# tailLite.net
KiCad netlist of a schematic drawn in Altium Designer
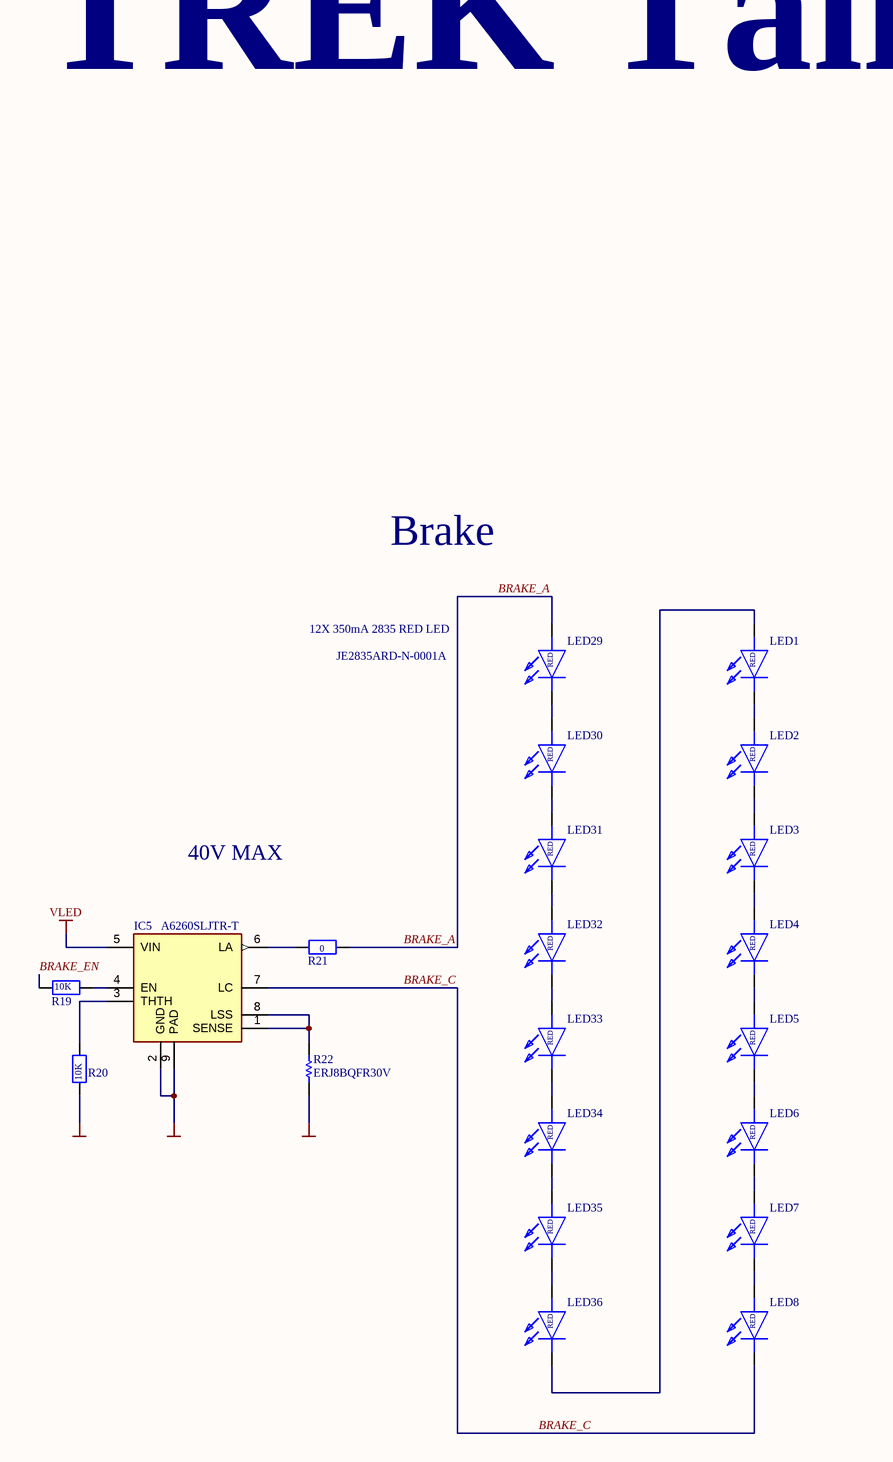
[diagram p0: tailLite.SchDoc, top left]
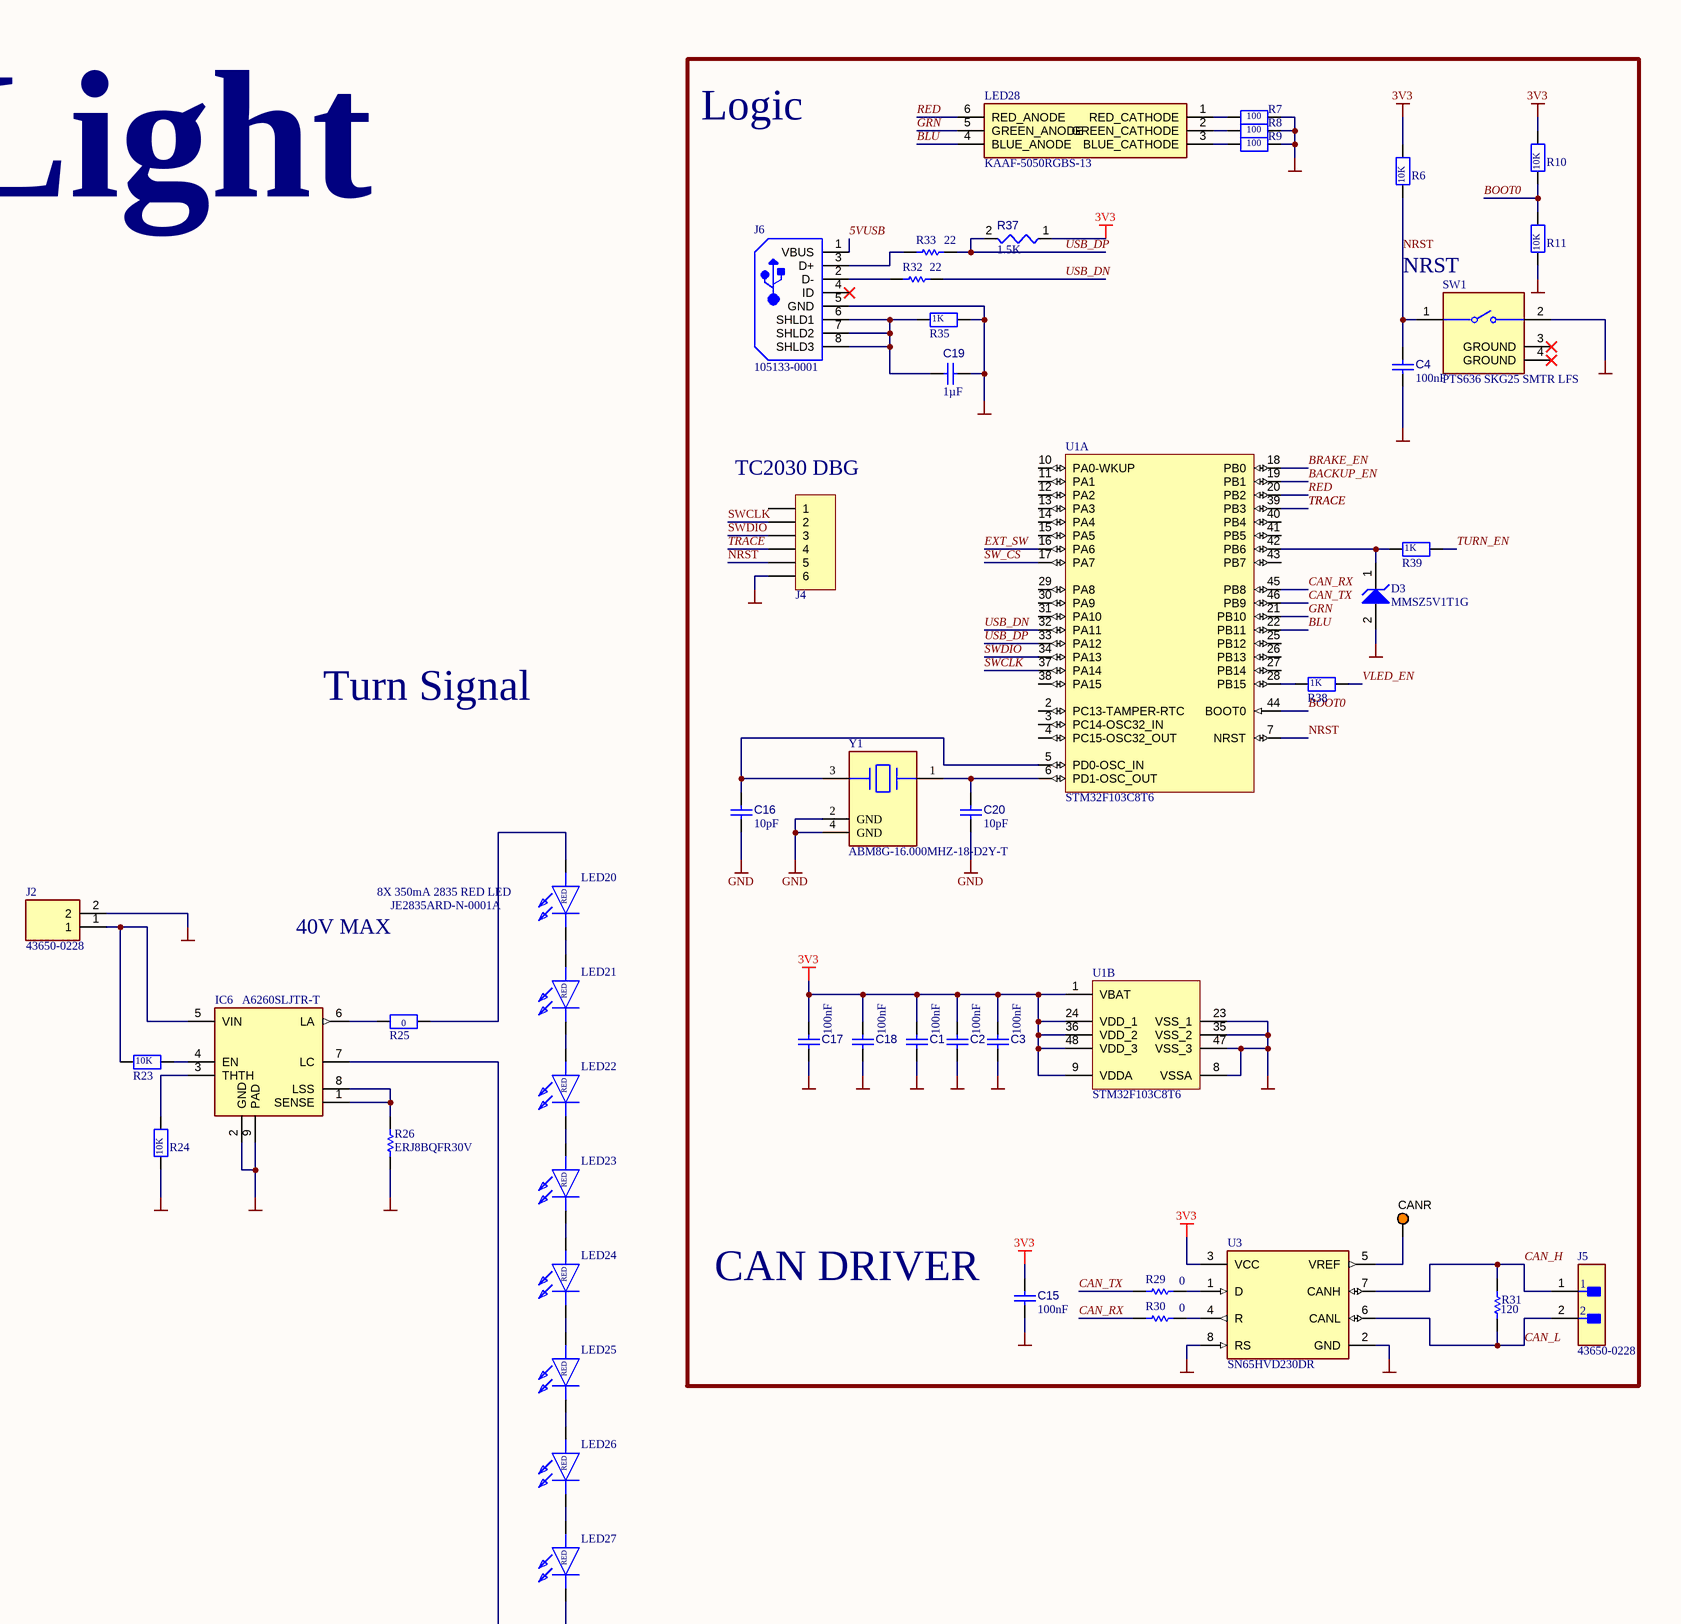
[diagram p1: tailLite.SchDoc, top right]
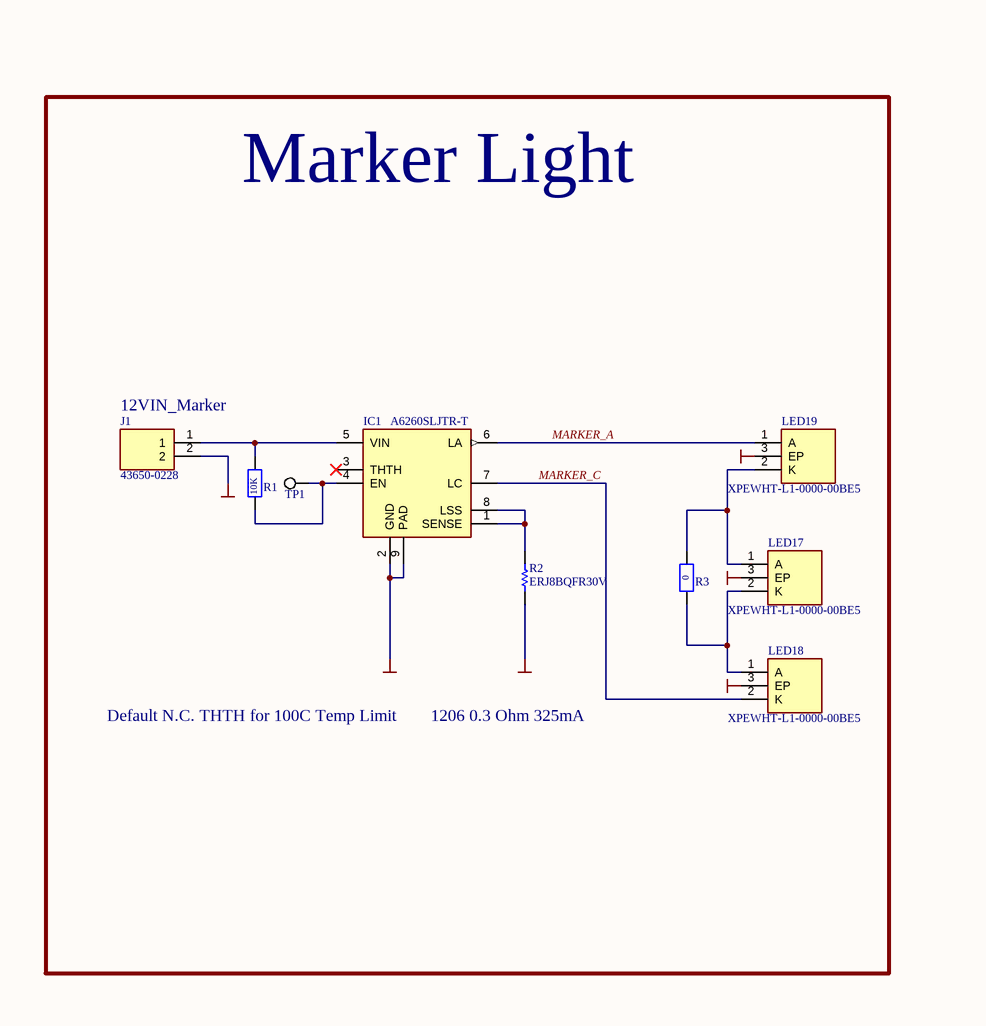
[diagram p2: tailLite.SchDoc, bottom left]
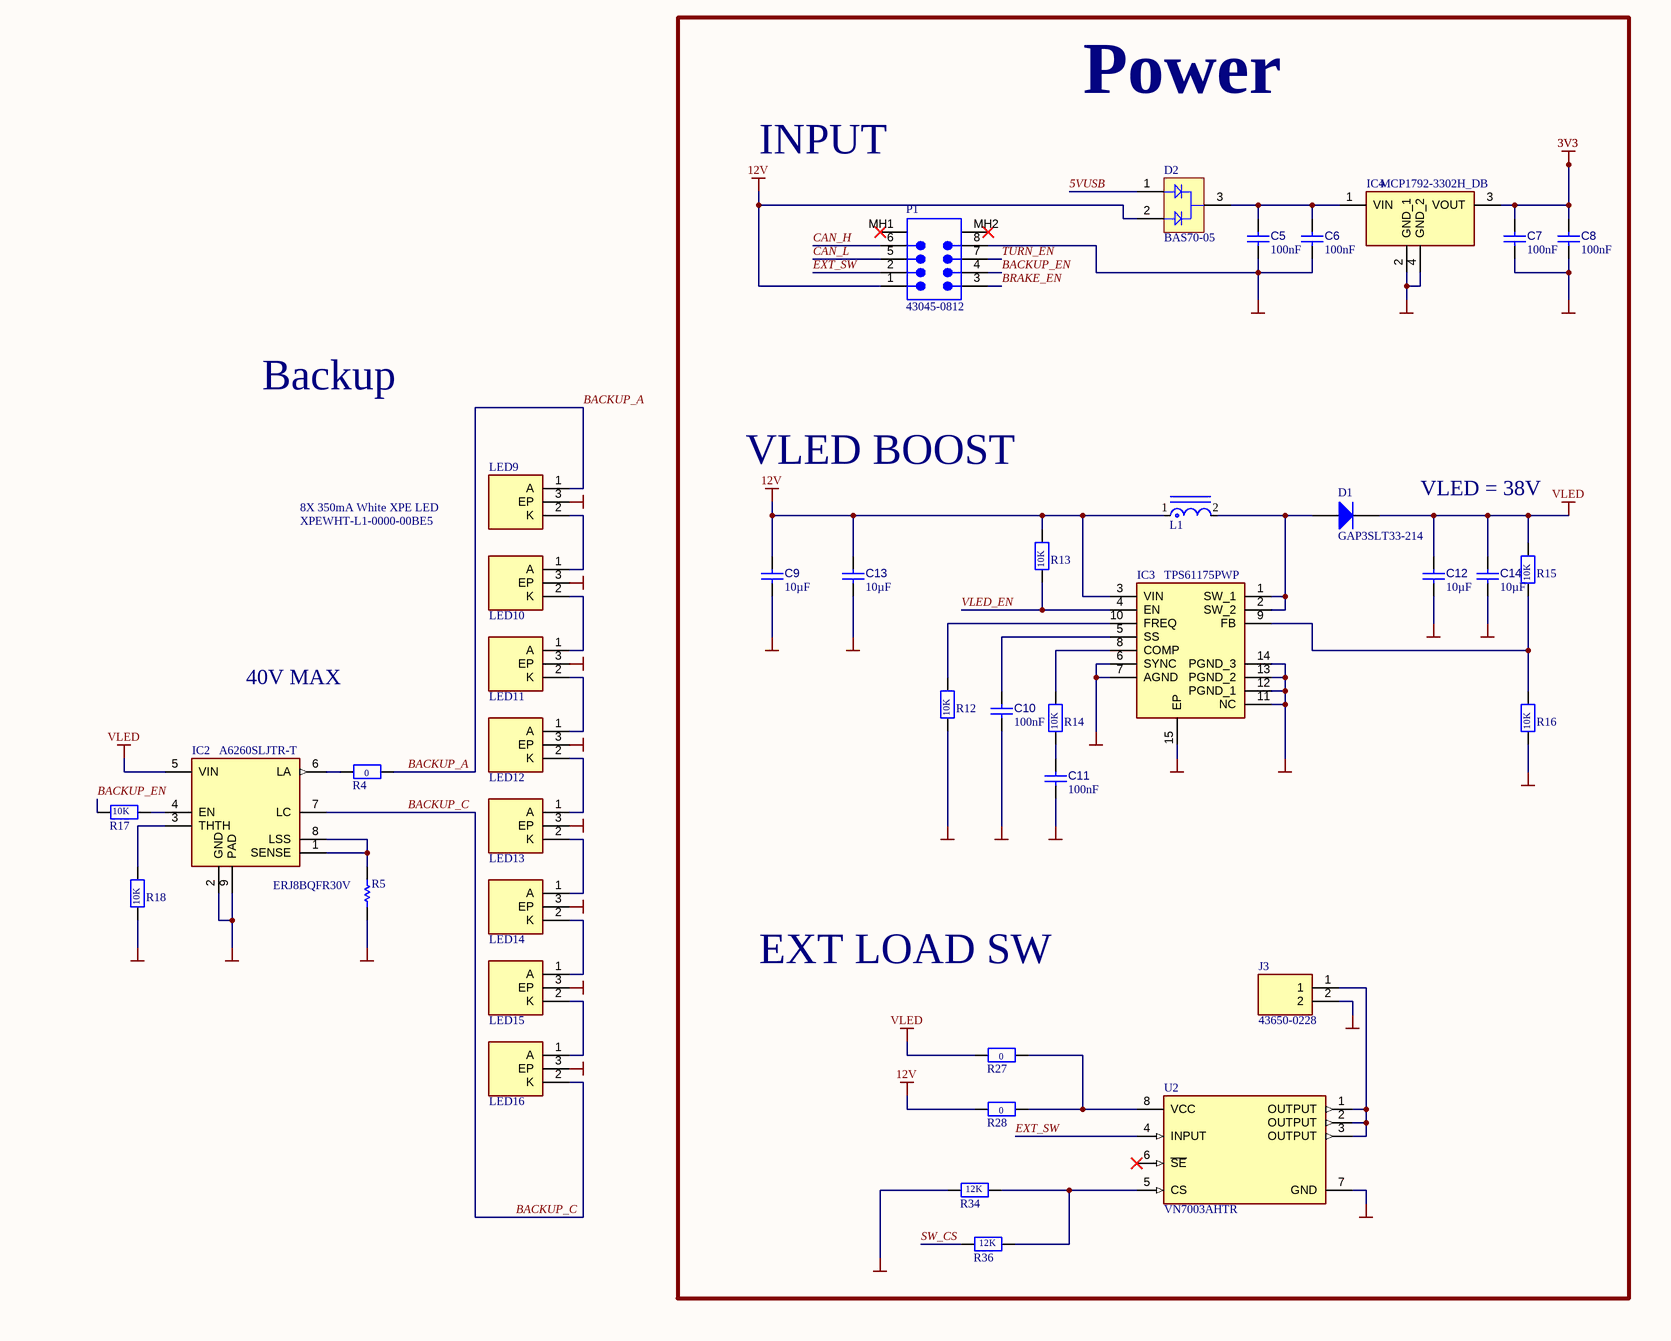
[diagram p3: tailLite.SchDoc, bottom right]

(export (version "E")
  (design (tool "Eeschema 10.0.6"))
  (components
    (comp (ref "C1")
      (value "100nF")
      (footprint "CAPC1608X90X40NL10T20")
      (description "Chip Capacitor, 100 nF, +/- 10%, 50 V, 0603 (1608 Metric)")
      (fields (field (name "TOLERANCE") "10%") (field (name "Comment") "Capacitor 100 nF +/-10% 50 V 0603"))
      (libsource (lib "Nebraska Instruments") (part "CAP-NP-2"))
    )
    (comp (ref "C2")
      (value "100nF")
      (footprint "CAPC1608X90X40NL10T20")
      (description "Chip Capacitor, 100 nF, +/- 10%, 50 V, 0603 (1608 Metric)")
      (fields (field (name "TOLERANCE") "10%") (field (name "Comment") "Capacitor 100 nF +/-10% 50 V 0603"))
      (libsource (lib "Nebraska Instruments") (part "CAP-NP-2"))
    )
    (comp (ref "C3")
      (value "100nF")
      (footprint "CAPC1608X90X40NL10T20")
      (description "Chip Capacitor, 100 nF, +/- 10%, 50 V, 0603 (1608 Metric)")
      (fields (field (name "TOLERANCE") "10%") (field (name "Comment") "Capacitor 100 nF +/-10% 50 V 0603"))
      (libsource (lib "Nebraska Instruments") (part "CAP-NP-2"))
    )
    (comp (ref "C4")
      (value "100nF")
      (footprint "CAPC1608X90X40NL10T20")
      (description "Chip Capacitor, 100 nF, +/- 10%, 50 V, 0603 (1608 Metric)")
      (fields (field (name "TOLERANCE") "10%") (field (name "Comment") "Capacitor 100 nF +/-10% 50 V 0603"))
      (libsource (lib "Nebraska Instruments") (part "CAP-NP-2"))
    )
    (comp (ref "C5")
      (value "100nF")
      (footprint "CAPC1608X90X40NL10T20")
      (description "Chip Capacitor, 100 nF, +/- 10%, 50 V, 0603 (1608 Metric)")
      (fields (field (name "TOLERANCE") "10%") (field (name "Comment") "Capacitor 100 nF +/-10% 50 V 0603"))
      (libsource (lib "Nebraska Instruments") (part "CAP-NP-2"))
    )
    (comp (ref "C6")
      (value "100nF")
      (footprint "CAPC1608X90X40NL10T20")
      (description "Chip Capacitor, 100 nF, +/- 10%, 50 V, 0603 (1608 Metric)")
      (fields (field (name "TOLERANCE") "10%") (field (name "Comment") "Capacitor 100 nF +/-10% 50 V 0603"))
      (libsource (lib "Nebraska Instruments") (part "CAP-NP-2"))
    )
    (comp (ref "C7")
      (value "100nF")
      (footprint "CAPC1608X90X40NL10T20")
      (description "Chip Capacitor, 100 nF, +/- 10%, 50 V, 0603 (1608 Metric)")
      (fields (field (name "TOLERANCE") "10%") (field (name "Comment") "Capacitor 100 nF +/-10% 50 V 0603"))
      (libsource (lib "Nebraska Instruments") (part "CAP-NP-2"))
    )
    (comp (ref "C8")
      (value "100nF")
      (footprint "CAPC1608X90X40NL10T20")
      (description "Chip Capacitor, 100 nF, +/- 10%, 50 V, 0603 (1608 Metric)")
      (fields (field (name "TOLERANCE") "10%") (field (name "Comment") "Capacitor 100 nF +/-10% 50 V 0603"))
      (libsource (lib "Nebraska Instruments") (part "CAP-NP-2"))
    )
    (comp (ref "C9")
      (value "10µF")
      (footprint "CAPC3216X180X50NL20T25")
      (description "Chip Capacitor, 10 uF, +/- 10%, 16 V, 1206 (3216 Metric)")
      (fields (field (name "TOLERANCE") "10%") (field (name "Comment") "Capacitor 10 uF +/- 10% 16 V 1206"))
      (libsource (lib "Nebraska Instruments") (part "CAP-NP-2"))
    )
    (comp (ref "C10")
      (value "100nF")
      (footprint "CAPC1608X90X40NL10T20")
      (description "Chip Capacitor, 100 nF, +/- 10%, 50 V, 0603 (1608 Metric)")
      (fields (field (name "TOLERANCE") "10%") (field (name "Comment") "Capacitor 100 nF +/-10% 50 V 0603"))
      (libsource (lib "Nebraska Instruments") (part "CAP-NP-2"))
    )
    (comp (ref "C11")
      (value "100nF")
      (footprint "CAPC1608X90X40NL10T20")
      (description "Chip Capacitor, 100 nF, +/- 10%, 50 V, 0603 (1608 Metric)")
      (fields (field (name "TOLERANCE") "10%") (field (name "Comment") "Capacitor 100 nF +/-10% 50 V 0603"))
      (libsource (lib "Nebraska Instruments") (part "CAP-NP-2"))
    )
    (comp (ref "C12")
      (value "10µF")
      (footprint "CAPC3216X180X50NL20T25")
      (description "Chip Capacitor, 10 uF, +/- 10%, 16 V, 1206 (3216 Metric)")
      (fields (field (name "TOLERANCE") "10%") (field (name "Comment") "Capacitor 10 uF +/- 10% 16 V 1206"))
      (libsource (lib "Nebraska Instruments") (part "CAP-NP-2"))
    )
    (comp (ref "C13")
      (value "10µF")
      (footprint "CAPC3216X180X50NL20T25")
      (description "Chip Capacitor, 10 uF, +/- 10%, 16 V, 1206 (3216 Metric)")
      (fields (field (name "TOLERANCE") "10%") (field (name "Comment") "Capacitor 10 uF +/- 10% 16 V 1206"))
      (libsource (lib "Nebraska Instruments") (part "CAP-NP-2"))
    )
    (comp (ref "C14")
      (value "10µF")
      (footprint "CAPC3216X180X50NL20T25")
      (description "Chip Capacitor, 10 uF, +/- 10%, 16 V, 1206 (3216 Metric)")
      (fields (field (name "TOLERANCE") "10%") (field (name "Comment") "Capacitor 10 uF +/- 10% 16 V 1206"))
      (libsource (lib "Nebraska Instruments") (part "CAP-NP-2"))
    )
    (comp (ref "C15")
      (value "100nF")
      (footprint "CAPC1608X90X40NL10T20")
      (description "Chip Capacitor, 100 nF, +/- 10%, 50 V, 0603 (1608 Metric)")
      (fields (field (name "TOLERANCE") "10%") (field (name "Comment") "Capacitor 100 nF +/-10% 50 V 0603"))
      (libsource (lib "Nebraska Instruments") (part "CAP-NP-2"))
    )
    (comp (ref "C16")
      (value "10pF")
      (footprint "CAPC1608X87X35NL15T15")
      (description "Chip Capacitor, 10 pF, +/- 0.25 pF, 50 V, 0603 (1608 Metric)")
      (fields
        (field (name "TOLERANCE") "0.25%")
        (field (name "Comment") "Capacitor 10 pF +/- 0.25 pF 50 V 0603")
      )
      (libsource (lib "Nebraska Instruments") (part "CAP-NP-2"))
    )
    (comp (ref "C17")
      (value "100nF")
      (footprint "CAPC1608X90X40NL10T20")
      (description "Chip Capacitor, 100 nF, +/- 10%, 50 V, 0603 (1608 Metric)")
      (fields (field (name "TOLERANCE") "10%") (field (name "Comment") "Capacitor 100 nF +/-10% 50 V 0603"))
      (libsource (lib "Nebraska Instruments") (part "CAP-NP-2"))
    )
    (comp (ref "C18")
      (value "100nF")
      (footprint "CAPC1608X90X40NL10T20")
      (description "Chip Capacitor, 100 nF, +/- 10%, 50 V, 0603 (1608 Metric)")
      (fields (field (name "TOLERANCE") "10%") (field (name "Comment") "Capacitor 100 nF +/-10% 50 V 0603"))
      (libsource (lib "Nebraska Instruments") (part "CAP-NP-2"))
    )
    (comp (ref "C19")
      (value "1µF")
      (footprint "CAPC1608X90X35ML15T15")
      (description "Chip Capacitor, 1 uF, +/- 10%, 16 V, 0603 (1608 Metric)")
      (fields (field (name "TOLERANCE") "10%") (field (name "Comment") "Capacitor 1uF +/- 10% 16V 0603"))
      (libsource (lib "Nebraska Instruments") (part "CAP-NP-2"))
    )
    (comp (ref "C20")
      (value "10pF")
      (footprint "CAPC1608X87X35NL15T15")
      (description "Chip Capacitor, 10 pF, +/- 0.25 pF, 50 V, 0603 (1608 Metric)")
      (fields
        (field (name "TOLERANCE") "0.25%")
        (field (name "Comment") "Capacitor 10 pF +/- 0.25 pF 50 V 0603")
      )
      (libsource (lib "Nebraska Instruments") (part "CAP-NP-2"))
    )
    (comp (ref "CANR")
      (value "5003")
      (footprint "KSTN-5003")
      (description "Test Point, Orange, Height 4.6 mm, Tail Length 3 mm, 1-Pin THD, RoHS")
      (fields (field (name "MANUFACTURER") "Keystone"))
      (libsource (lib "Nebraska Instruments") (part "TESTPOINT_ORANGE"))
    )
    (comp (ref "D1")
      (value "GAP3SLT33-214")
      (footprint "GESC-GAP3SLT33-214-2_V")
      (fields (field (name "MANUFACTURER") "GeneSiCSemiconductor"))
      (libsource (lib "Altium Content Vault") (part "D-AK-2"))
    )
    (comp (ref "D2")
      (value "BAS70-05")
      (footprint "INF-SOT23_N")
      (description "Rectifier Diode Schottky Si 0.07A Automotive 3-Pin SOT-23 T/R")
      (libsource (lib "Nebraska Instruments") (part "INF-D_A1A2K3-3_A"))
    )
    (comp (ref "D3")
      (value "MMSZ5V1T1G")
      (footprint "ONSC-SOD-123-2-425-04_V")
      (description "Zener Diode Single 5.1V 5% 60Ohm 500mW 2-Pin SOD-123 T/R")
      (libsource (lib "Nebraska Instruments") (part "MMSZ5V1T1G"))
    )
    (comp (ref "IC1")
      (value "A6260SLJTR-T")
      (footprint "SamacSys:SOIC127P600X170-9N")
      (description "Integrated Circuit")
      (libsource (lib "") (part "A6260SLJTR-T_1"))
    )
    (comp (ref "IC2")
      (value "A6260SLJTR-T")
      (footprint "SamacSys:SOIC127P600X170-9N")
      (description "Integrated Circuit")
      (libsource (lib "*") (part "A6260SLJTR-T"))
    )
    (comp (ref "IC3")
      (value "TPS61175PWP")
      (footprint "SamacSys:SOP65P640X120-15N")
      (description "Integrated Circuit")
      (fields (field (name "MOUSER PART NUMBER") "595-TPS61175PWP"))
      (libsource (lib "*") (part "TPS61175PWP"))
    )
    (comp (ref "IC4")
      (value "MCP1792-3302H_DB")
      (footprint "SOT230P700X180-4N")
      (description "LDO Voltage Regulators High input voltage regulator 3.3V 3Ld SOT-223")
      (fields
        (field (name "MANUFACTURER_PART_NUMBER") "MCP1792-3302H/DB")
        (field (name "MOUSER PART NUMBER") "579-MCP1792-3302HDB")
      )
      (libsource (lib "Nebraska Instruments") (part "MCP1792-5002H_DB"))
    )
    (comp (ref "IC5")
      (value "A6260SLJTR-T")
      (footprint "SamacSys:SOIC127P600X170-9N")
      (description "Integrated Circuit")
      (libsource (lib "*") (part "A6260SLJTR-T"))
    )
    (comp (ref "IC6")
      (value "A6260SLJTR-T")
      (footprint "SamacSys:SOIC127P600X170-9N")
      (description "Integrated Circuit")
      (libsource (lib "*") (part "A6260SLJTR-T"))
    )
    (comp (ref "J1")
      (value "43650-0228")
      (footprint "SamacSys:43650-02YY_272829")
      (description "Connector")
      (fields (field (name "MOUSER PART NUMBER") "538-43650-0228"))
      (libsource (lib "*") (part "43650-0228"))
    )
    (comp (ref "J2")
      (value "43650-0228")
      (footprint "SamacSys:43650-02YY_272829")
      (description "Connector")
      (fields (field (name "MOUSER PART NUMBER") "538-43650-0228"))
      (libsource (lib "") (part "43650-0228_1"))
    )
    (comp (ref "J3")
      (value "43650-0228")
      (footprint "SamacSys:43650-02YY_272829")
      (description "Connector")
      (fields (field (name "MOUSER PART NUMBER") "538-43650-0228"))
      (libsource (lib "*") (part "43650-0228"))
    )
    (comp (ref "J4")
      (value "ICSP")
      (footprint "TC2030-MCP-NL")
      (libsource (lib "Nebraska Instruments") (part "ICSP"))
    )
    (comp (ref "J5")
      (value "43650-0228")
      (footprint "FP-43650-0228-MFG")
      (description "CONN HEADER VERT 2POS 3MM")
      (libsource (lib "Altium Content Vault") (part "3bc925449376181038e59eaffc5286c"))
    )
    (comp (ref "J6")
      (value "105133-0001")
      (footprint "MOLX-105133-0001_V")
      (description "Conn Micro USB 2.0 Type B RCP 5 POS 0.65mm Solder ST SMD 5 Terminal 1 Port Micro-USB T/R")
      (libsource (lib "Nebraska Instruments") (part "USB-5-3SHLD"))
    )
    (comp (ref "L1")
      (value "HCM0703-3R3-R")
      (footprint "FP-HCM0703-MFG")
      (description "Inductor Power Shielded Wirewound 3.3uH/1.98uH 20% 100KHz Powdered Iron 6A 30mOhm DCR T/R")
      (libsource (lib "Nebraska Instruments") (part "39f40dd458ca4f5319b423cc0fb7879"))
    )
    (comp (ref "LED1")
      (value "JE2835ARD-N-0001A")
      (footprint "JE2835ARDN0001A0000N0000001")
      (description "LED Lighting Color J Red-Orange 615nm (610nm ~ 620nm) 1411 (3528 Metric)")
      (fields
        (field (name "MANUFACTURER_PART_NUMBER") "JE2835ARD-N-0001A0000-N0000001")
        (field (name "MOUSER PART NUMBER") "941-JE2835ARDN01AN")
      )
      (libsource (lib "Nebraska Instruments") (part "JE2835ARY-N-0002A0000-N0000001"))
    )
    (comp (ref "LED2")
      (value "JE2835ARD-N-0001A")
      (footprint "JE2835ARDN0001A0000N0000001")
      (description "LED Lighting Color J Red-Orange 615nm (610nm ~ 620nm) 1411 (3528 Metric)")
      (fields
        (field (name "MANUFACTURER_PART_NUMBER") "JE2835ARD-N-0001A0000-N0000001")
        (field (name "MOUSER PART NUMBER") "941-JE2835ARDN01AN")
      )
      (libsource (lib "Nebraska Instruments") (part "JE2835ARY-N-0002A0000-N0000001"))
    )
    (comp (ref "LED3")
      (value "JE2835ARD-N-0001A")
      (footprint "JE2835ARDN0001A0000N0000001")
      (description "LED Lighting Color J Red-Orange 615nm (610nm ~ 620nm) 1411 (3528 Metric)")
      (fields
        (field (name "MANUFACTURER_PART_NUMBER") "JE2835ARD-N-0001A0000-N0000001")
        (field (name "MOUSER PART NUMBER") "941-JE2835ARDN01AN")
      )
      (libsource (lib "Nebraska Instruments") (part "JE2835ARY-N-0002A0000-N0000001"))
    )
    (comp (ref "LED4")
      (value "JE2835ARD-N-0001A")
      (footprint "JE2835ARDN0001A0000N0000001")
      (description "LED Lighting Color J Red-Orange 615nm (610nm ~ 620nm) 1411 (3528 Metric)")
      (fields
        (field (name "MANUFACTURER_PART_NUMBER") "JE2835ARD-N-0001A0000-N0000001")
        (field (name "MOUSER PART NUMBER") "941-JE2835ARDN01AN")
      )
      (libsource (lib "Nebraska Instruments") (part "JE2835ARY-N-0002A0000-N0000001"))
    )
    (comp (ref "LED5")
      (value "JE2835ARD-N-0001A")
      (footprint "JE2835ARDN0001A0000N0000001")
      (description "LED Lighting Color J Red-Orange 615nm (610nm ~ 620nm) 1411 (3528 Metric)")
      (fields
        (field (name "MANUFACTURER_PART_NUMBER") "JE2835ARD-N-0001A0000-N0000001")
        (field (name "MOUSER PART NUMBER") "941-JE2835ARDN01AN")
      )
      (libsource (lib "Nebraska Instruments") (part "JE2835ARY-N-0002A0000-N0000001"))
    )
    (comp (ref "LED6")
      (value "JE2835ARD-N-0001A")
      (footprint "JE2835ARDN0001A0000N0000001")
      (description "LED Lighting Color J Red-Orange 615nm (610nm ~ 620nm) 1411 (3528 Metric)")
      (fields
        (field (name "MANUFACTURER_PART_NUMBER") "JE2835ARD-N-0001A0000-N0000001")
        (field (name "MOUSER PART NUMBER") "941-JE2835ARDN01AN")
      )
      (libsource (lib "Nebraska Instruments") (part "JE2835ARY-N-0002A0000-N0000001"))
    )
    (comp (ref "LED7")
      (value "JE2835ARD-N-0001A")
      (footprint "JE2835ARDN0001A0000N0000001")
      (description "LED Lighting Color J Red-Orange 615nm (610nm ~ 620nm) 1411 (3528 Metric)")
      (fields
        (field (name "MANUFACTURER_PART_NUMBER") "JE2835ARD-N-0001A0000-N0000001")
        (field (name "MOUSER PART NUMBER") "941-JE2835ARDN01AN")
      )
      (libsource (lib "Nebraska Instruments") (part "JE2835ARY-N-0002A0000-N0000001"))
    )
    (comp (ref "LED8")
      (value "JE2835ARD-N-0001A")
      (footprint "JE2835ARDN0001A0000N0000001")
      (description "LED Lighting Color J Red-Orange 615nm (610nm ~ 620nm) 1411 (3528 Metric)")
      (fields
        (field (name "MANUFACTURER_PART_NUMBER") "JE2835ARD-N-0001A0000-N0000001")
        (field (name "MOUSER PART NUMBER") "941-JE2835ARDN01AN")
      )
      (libsource (lib "Nebraska Instruments") (part "JE2835ARY-N-0002A0000-N0000001"))
    )
    (comp (ref "LED9")
      (value "XPEWHT-L1-0000-00BE5")
      (footprint "XPEWHTL1000000BE5")
      (description "LED")
      (fields (field (name "MOUSER PART NUMBER") "941-XPEWHTL100BE5"))
      (libsource (lib "Nebraska Instruments") (part "XPEWHT-L1-0000-00BE5"))
    )
    (comp (ref "LED10")
      (value "XPEWHT-L1-0000-00BE5")
      (footprint "XPEWHTL1000000BE5")
      (description "LED")
      (fields (field (name "MOUSER PART NUMBER") "941-XPEWHTL100BE5"))
      (libsource (lib "Nebraska Instruments") (part "XPEWHT-L1-0000-00BE5"))
    )
    (comp (ref "LED11")
      (value "XPEWHT-L1-0000-00BE5")
      (footprint "XPEWHTL1000000BE5")
      (description "LED")
      (fields (field (name "MOUSER PART NUMBER") "941-XPEWHTL100BE5"))
      (libsource (lib "Nebraska Instruments") (part "XPEWHT-L1-0000-00BE5"))
    )
    (comp (ref "LED12")
      (value "XPEWHT-L1-0000-00BE5")
      (footprint "XPEWHTL1000000BE5")
      (description "LED")
      (fields (field (name "MOUSER PART NUMBER") "941-XPEWHTL100BE5"))
      (libsource (lib "Nebraska Instruments") (part "XPEWHT-L1-0000-00BE5"))
    )
    (comp (ref "LED13")
      (value "XPEWHT-L1-0000-00BE5")
      (footprint "XPEWHTL1000000BE5")
      (description "LED")
      (fields (field (name "MOUSER PART NUMBER") "941-XPEWHTL100BE5"))
      (libsource (lib "Nebraska Instruments") (part "XPEWHT-L1-0000-00BE5"))
    )
    (comp (ref "LED14")
      (value "XPEWHT-L1-0000-00BE5")
      (footprint "XPEWHTL1000000BE5")
      (description "LED")
      (fields (field (name "MOUSER PART NUMBER") "941-XPEWHTL100BE5"))
      (libsource (lib "Nebraska Instruments") (part "XPEWHT-L1-0000-00BE5"))
    )
    (comp (ref "LED15")
      (value "XPEWHT-L1-0000-00BE5")
      (footprint "XPEWHTL1000000BE5")
      (description "LED")
      (fields (field (name "MOUSER PART NUMBER") "941-XPEWHTL100BE5"))
      (libsource (lib "Nebraska Instruments") (part "XPEWHT-L1-0000-00BE5"))
    )
    (comp (ref "LED16")
      (value "XPEWHT-L1-0000-00BE5")
      (footprint "XPEWHTL1000000BE5")
      (description "LED")
      (fields (field (name "MOUSER PART NUMBER") "941-XPEWHTL100BE5"))
      (libsource (lib "Nebraska Instruments") (part "XPEWHT-L1-0000-00BE5"))
    )
    (comp (ref "LED17")
      (value "XPEWHT-L1-0000-00BE5")
      (footprint "XPEWHTL1000000BE5")
      (description "LED")
      (fields (field (name "MOUSER PART NUMBER") "941-XPEWHTL100BE5"))
      (libsource (lib "") (part "XPEWHT-L1-0000-00BE5_1"))
    )
    (comp (ref "LED18")
      (value "XPEWHT-L1-0000-00BE5")
      (footprint "XPEWHTL1000000BE5")
      (description "LED")
      (fields (field (name "MOUSER PART NUMBER") "941-XPEWHTL100BE5"))
      (libsource (lib "") (part "XPEWHT-L1-0000-00BE5_1"))
    )
    (comp (ref "LED19")
      (value "XPEWHT-L1-0000-00BE5")
      (footprint "XPEWHTL1000000BE5")
      (description "LED")
      (fields (field (name "MOUSER PART NUMBER") "941-XPEWHTL100BE5"))
      (libsource (lib "") (part "XPEWHT-L1-0000-00BE5_1"))
    )
    (comp (ref "LED20")
      (value "JE2835ARD-N-0001A")
      (footprint "JE2835ARDN0001A0000N0000001")
      (description "LED Lighting Color J Red-Orange 615nm (610nm ~ 620nm) 1411 (3528 Metric)")
      (fields
        (field (name "MANUFACTURER_PART_NUMBER") "JE2835ARD-N-0001A0000-N0000001")
        (field (name "MOUSER PART NUMBER") "941-JE2835ARDN01AN")
      )
      (libsource (lib "Nebraska Instruments") (part "JE2835ARY-N-0002A0000-N0000001"))
    )
    (comp (ref "LED21")
      (value "JE2835ARD-N-0001A")
      (footprint "JE2835ARDN0001A0000N0000001")
      (description "LED Lighting Color J Red-Orange 615nm (610nm ~ 620nm) 1411 (3528 Metric)")
      (fields
        (field (name "MANUFACTURER_PART_NUMBER") "JE2835ARD-N-0001A0000-N0000001")
        (field (name "MOUSER PART NUMBER") "941-JE2835ARDN01AN")
      )
      (libsource (lib "Nebraska Instruments") (part "JE2835ARY-N-0002A0000-N0000001"))
    )
    (comp (ref "LED22")
      (value "JE2835ARD-N-0001A")
      (footprint "JE2835ARDN0001A0000N0000001")
      (description "LED Lighting Color J Red-Orange 615nm (610nm ~ 620nm) 1411 (3528 Metric)")
      (fields
        (field (name "MANUFACTURER_PART_NUMBER") "JE2835ARD-N-0001A0000-N0000001")
        (field (name "MOUSER PART NUMBER") "941-JE2835ARDN01AN")
      )
      (libsource (lib "Nebraska Instruments") (part "JE2835ARY-N-0002A0000-N0000001"))
    )
    (comp (ref "LED23")
      (value "JE2835ARD-N-0001A")
      (footprint "JE2835ARDN0001A0000N0000001")
      (description "LED Lighting Color J Red-Orange 615nm (610nm ~ 620nm) 1411 (3528 Metric)")
      (fields
        (field (name "MANUFACTURER_PART_NUMBER") "JE2835ARD-N-0001A0000-N0000001")
        (field (name "MOUSER PART NUMBER") "941-JE2835ARDN01AN")
      )
      (libsource (lib "Nebraska Instruments") (part "JE2835ARY-N-0002A0000-N0000001"))
    )
    (comp (ref "LED24")
      (value "JE2835ARD-N-0001A")
      (footprint "JE2835ARDN0001A0000N0000001")
      (description "LED Lighting Color J Red-Orange 615nm (610nm ~ 620nm) 1411 (3528 Metric)")
      (fields
        (field (name "MANUFACTURER_PART_NUMBER") "JE2835ARD-N-0001A0000-N0000001")
        (field (name "MOUSER PART NUMBER") "941-JE2835ARDN01AN")
      )
      (libsource (lib "Nebraska Instruments") (part "JE2835ARY-N-0002A0000-N0000001"))
    )
    (comp (ref "LED25")
      (value "JE2835ARD-N-0001A")
      (footprint "JE2835ARDN0001A0000N0000001")
      (description "LED Lighting Color J Red-Orange 615nm (610nm ~ 620nm) 1411 (3528 Metric)")
      (fields
        (field (name "MANUFACTURER_PART_NUMBER") "JE2835ARD-N-0001A0000-N0000001")
        (field (name "MOUSER PART NUMBER") "941-JE2835ARDN01AN")
      )
      (libsource (lib "Nebraska Instruments") (part "JE2835ARY-N-0002A0000-N0000001"))
    )
    (comp (ref "LED26")
      (value "JE2835ARD-N-0001A")
      (footprint "JE2835ARDN0001A0000N0000001")
      (description "LED Lighting Color J Red-Orange 615nm (610nm ~ 620nm) 1411 (3528 Metric)")
      (fields
        (field (name "MANUFACTURER_PART_NUMBER") "JE2835ARD-N-0001A0000-N0000001")
        (field (name "MOUSER PART NUMBER") "941-JE2835ARDN01AN")
      )
      (libsource (lib "Nebraska Instruments") (part "JE2835ARY-N-0002A0000-N0000001"))
    )
    (comp (ref "LED27")
      (value "JE2835ARD-N-0001A")
      (footprint "JE2835ARDN0001A0000N0000001")
      (description "LED Lighting Color J Red-Orange 615nm (610nm ~ 620nm) 1411 (3528 Metric)")
      (fields
        (field (name "MANUFACTURER_PART_NUMBER") "JE2835ARD-N-0001A0000-N0000001")
        (field (name "MOUSER PART NUMBER") "941-JE2835ARDN01AN")
      )
      (libsource (lib "Nebraska Instruments") (part "JE2835ARY-N-0002A0000-N0000001"))
    )
    (comp (ref "LED28")
      (value "KAAF-5050RGBS-13")
      (footprint "SamacSys:KAAF-5050RGBS-13")
      (description "LED")
      (libsource (lib "*") (part "KAAF-5050RGBS-13"))
    )
    (comp (ref "LED29")
      (value "JE2835ARD-N-0001A")
      (footprint "JE2835ARDN0001A0000N0000001")
      (description "LED Lighting Color J Red-Orange 615nm (610nm ~ 620nm) 1411 (3528 Metric)")
      (fields
        (field (name "MANUFACTURER_PART_NUMBER") "JE2835ARD-N-0001A0000-N0000001")
        (field (name "MOUSER PART NUMBER") "941-JE2835ARDN01AN")
      )
      (libsource (lib "Nebraska Instruments") (part "JE2835ARY-N-0002A0000-N0000001"))
    )
    (comp (ref "LED30")
      (value "JE2835ARD-N-0001A")
      (footprint "JE2835ARDN0001A0000N0000001")
      (description "LED Lighting Color J Red-Orange 615nm (610nm ~ 620nm) 1411 (3528 Metric)")
      (fields
        (field (name "MANUFACTURER_PART_NUMBER") "JE2835ARD-N-0001A0000-N0000001")
        (field (name "MOUSER PART NUMBER") "941-JE2835ARDN01AN")
      )
      (libsource (lib "Nebraska Instruments") (part "JE2835ARY-N-0002A0000-N0000001"))
    )
    (comp (ref "LED31")
      (value "JE2835ARD-N-0001A")
      (footprint "JE2835ARDN0001A0000N0000001")
      (description "LED Lighting Color J Red-Orange 615nm (610nm ~ 620nm) 1411 (3528 Metric)")
      (fields
        (field (name "MANUFACTURER_PART_NUMBER") "JE2835ARD-N-0001A0000-N0000001")
        (field (name "MOUSER PART NUMBER") "941-JE2835ARDN01AN")
      )
      (libsource (lib "Nebraska Instruments") (part "JE2835ARY-N-0002A0000-N0000001"))
    )
    (comp (ref "LED32")
      (value "JE2835ARD-N-0001A")
      (footprint "JE2835ARDN0001A0000N0000001")
      (description "LED Lighting Color J Red-Orange 615nm (610nm ~ 620nm) 1411 (3528 Metric)")
      (fields
        (field (name "MANUFACTURER_PART_NUMBER") "JE2835ARD-N-0001A0000-N0000001")
        (field (name "MOUSER PART NUMBER") "941-JE2835ARDN01AN")
      )
      (libsource (lib "Nebraska Instruments") (part "JE2835ARY-N-0002A0000-N0000001"))
    )
    (comp (ref "LED33")
      (value "JE2835ARD-N-0001A")
      (footprint "JE2835ARDN0001A0000N0000001")
      (description "LED Lighting Color J Red-Orange 615nm (610nm ~ 620nm) 1411 (3528 Metric)")
      (fields
        (field (name "MANUFACTURER_PART_NUMBER") "JE2835ARD-N-0001A0000-N0000001")
        (field (name "MOUSER PART NUMBER") "941-JE2835ARDN01AN")
      )
      (libsource (lib "Nebraska Instruments") (part "JE2835ARY-N-0002A0000-N0000001"))
    )
    (comp (ref "LED34")
      (value "JE2835ARD-N-0001A")
      (footprint "JE2835ARDN0001A0000N0000001")
      (description "LED Lighting Color J Red-Orange 615nm (610nm ~ 620nm) 1411 (3528 Metric)")
      (fields
        (field (name "MANUFACTURER_PART_NUMBER") "JE2835ARD-N-0001A0000-N0000001")
        (field (name "MOUSER PART NUMBER") "941-JE2835ARDN01AN")
      )
      (libsource (lib "Nebraska Instruments") (part "JE2835ARY-N-0002A0000-N0000001"))
    )
    (comp (ref "LED35")
      (value "JE2835ARD-N-0001A")
      (footprint "JE2835ARDN0001A0000N0000001")
      (description "LED Lighting Color J Red-Orange 615nm (610nm ~ 620nm) 1411 (3528 Metric)")
      (fields
        (field (name "MANUFACTURER_PART_NUMBER") "JE2835ARD-N-0001A0000-N0000001")
        (field (name "MOUSER PART NUMBER") "941-JE2835ARDN01AN")
      )
      (libsource (lib "Nebraska Instruments") (part "JE2835ARY-N-0002A0000-N0000001"))
    )
    (comp (ref "LED36")
      (value "JE2835ARD-N-0001A")
      (footprint "JE2835ARDN0001A0000N0000001")
      (description "LED Lighting Color J Red-Orange 615nm (610nm ~ 620nm) 1411 (3528 Metric)")
      (fields
        (field (name "MANUFACTURER_PART_NUMBER") "JE2835ARD-N-0001A0000-N0000001")
        (field (name "MOUSER PART NUMBER") "941-JE2835ARDN01AN")
      )
      (libsource (lib "Nebraska Instruments") (part "JE2835ARY-N-0002A0000-N0000001"))
    )
    (comp (ref "P1")
      (value "43045-0812")
      (footprint "MOLX-43045-0812_V")
      (libsource (lib "Altium Content Vault") (part "MOLX-43045-0812"))
    )
    (comp (ref "R1")
      (value "0603_10K")
      (footprint "RESC1609X55X30ML15T15")
      (description "SMD Chip Resistor, 1.67 kohm, ± 1%, 100 mW, 0603 [1608 Metric], Thick Film, Precision")
      (libsource (lib "Nebraska Instruments") (part "RES-2"))
    )
    (comp (ref "R2")
      (value "ERJ8BQFR30V")
      (footprint "RESC3216X70X50LL05T20")
      (fields (field (name "MANUFACTURER") "Panasonic"))
      (libsource (lib "Altium Content Vault") (part "RES"))
    )
    (comp (ref "R3")
      (value "0603_0ohm")
      (footprint "RESC1609X55X30ML15T15")
      (description "SMD Chip Resistor, 0ohm, ± 1%, 100 mW, 0603 [1608 Metric], Thick Film, Precision")
      (libsource (lib "") (part "RES-2_1"))
    )
    (comp (ref "R4")
      (value "0603_0ohm")
      (footprint "RESC1609X55X30ML15T15")
      (description "SMD Chip Resistor, 0ohm, ± 1%, 100 mW, 0603 [1608 Metric], Thick Film, Precision")
      (libsource (lib "") (part "RES-2_1"))
    )
    (comp (ref "R5")
      (value "ERJ8BQFR30V")
      (footprint "RESC3216X70X50LL05T20")
      (fields (field (name "MANUFACTURER") "Panasonic"))
      (libsource (lib "Altium Content Vault") (part "RES"))
    )
    (comp (ref "R6")
      (value "0603_10K")
      (footprint "RESC1609X55X30ML15T15")
      (description "SMD Chip Resistor, 1.67 kohm, ± 1%, 100 mW, 0603 [1608 Metric], Thick Film, Precision")
      (libsource (lib "Nebraska Instruments") (part "RES-2"))
    )
    (comp (ref "R7")
      (value "0603_100ohm")
      (footprint "RESC1609X55X30ML15T15")
      (description "SMD Chip Resistor, 100 ohm, ± 1%, 100 mW, 0603 [1608 Metric], Thick Film, Precision")
      (libsource (lib "") (part "RES-2_2"))
    )
    (comp (ref "R8")
      (value "0603_100ohm")
      (footprint "RESC1609X55X30ML15T15")
      (description "SMD Chip Resistor, 100 ohm, ± 1%, 100 mW, 0603 [1608 Metric], Thick Film, Precision")
      (libsource (lib "") (part "RES-2_2"))
    )
    (comp (ref "R9")
      (value "0603_100ohm")
      (footprint "RESC1609X55X30ML15T15")
      (description "SMD Chip Resistor, 100 ohm, ± 1%, 100 mW, 0603 [1608 Metric], Thick Film, Precision")
      (libsource (lib "") (part "RES-2_2"))
    )
    (comp (ref "R10")
      (value "0603_10K")
      (footprint "RESC1609X55X30ML15T15")
      (description "SMD Chip Resistor, 1.67 kohm, ± 1%, 100 mW, 0603 [1608 Metric], Thick Film, Precision")
      (libsource (lib "Nebraska Instruments") (part "RES-2"))
    )
    (comp (ref "R11")
      (value "0603_10K")
      (footprint "RESC1609X55X30ML15T15")
      (description "SMD Chip Resistor, 1.67 kohm, ± 1%, 100 mW, 0603 [1608 Metric], Thick Film, Precision")
      (libsource (lib "Nebraska Instruments") (part "RES-2"))
    )
    (comp (ref "R12")
      (value "0603_10K")
      (footprint "RESC1609X55X30ML15T15")
      (description "SMD Chip Resistor, 1.67 kohm, ± 1%, 100 mW, 0603 [1608 Metric], Thick Film, Precision")
      (libsource (lib "Nebraska Instruments") (part "RES-2"))
    )
    (comp (ref "R13")
      (value "0603_10K")
      (footprint "RESC1609X55X30ML15T15")
      (description "SMD Chip Resistor, 1.67 kohm, ± 1%, 100 mW, 0603 [1608 Metric], Thick Film, Precision")
      (libsource (lib "Nebraska Instruments") (part "RES-2"))
    )
    (comp (ref "R14")
      (value "0603_10K")
      (footprint "RESC1609X55X30ML15T15")
      (description "SMD Chip Resistor, 1.67 kohm, ± 1%, 100 mW, 0603 [1608 Metric], Thick Film, Precision")
      (libsource (lib "Nebraska Instruments") (part "RES-2"))
    )
    (comp (ref "R15")
      (value "0603_10K")
      (footprint "RESC1609X55X30ML15T15")
      (description "SMD Chip Resistor, 1.67 kohm, ± 1%, 100 mW, 0603 [1608 Metric], Thick Film, Precision")
      (libsource (lib "Nebraska Instruments") (part "RES-2"))
    )
    (comp (ref "R16")
      (value "0603_10K")
      (footprint "RESC1609X55X30ML15T15")
      (description "SMD Chip Resistor, 1.67 kohm, ± 1%, 100 mW, 0603 [1608 Metric], Thick Film, Precision")
      (libsource (lib "Nebraska Instruments") (part "RES-2"))
    )
    (comp (ref "R17")
      (value "0603_10K")
      (footprint "RESC1609X55X30ML15T15")
      (description "SMD Chip Resistor, 1.67 kohm, ± 1%, 100 mW, 0603 [1608 Metric], Thick Film, Precision")
      (libsource (lib "Nebraska Instruments") (part "RES-2"))
    )
    (comp (ref "R18")
      (value "0603_10K")
      (footprint "RESC1609X55X30ML15T15")
      (description "SMD Chip Resistor, 1.67 kohm, ± 1%, 100 mW, 0603 [1608 Metric], Thick Film, Precision")
      (libsource (lib "Nebraska Instruments") (part "RES-2"))
    )
    (comp (ref "R19")
      (value "0603_10K")
      (footprint "RESC1609X55X30ML15T15")
      (description "SMD Chip Resistor, 1.67 kohm, ± 1%, 100 mW, 0603 [1608 Metric], Thick Film, Precision")
      (libsource (lib "Nebraska Instruments") (part "RES-2"))
    )
    (comp (ref "R20")
      (value "0603_10K")
      (footprint "RESC1609X55X30ML15T15")
      (description "SMD Chip Resistor, 1.67 kohm, ± 1%, 100 mW, 0603 [1608 Metric], Thick Film, Precision")
      (libsource (lib "Nebraska Instruments") (part "RES-2"))
    )
    (comp (ref "R21")
      (value "0603_0ohm")
      (footprint "RESC1609X55X30ML15T15")
      (description "SMD Chip Resistor, 0ohm, ± 1%, 100 mW, 0603 [1608 Metric], Thick Film, Precision")
      (libsource (lib "") (part "RES-2_1"))
    )
    (comp (ref "R22")
      (value "ERJ8BQFR30V")
      (footprint "RESC3216X70X50LL05T20")
      (fields (field (name "MANUFACTURER") "Panasonic"))
      (libsource (lib "Altium Content Vault") (part "RES"))
    )
    (comp (ref "R23")
      (value "0603_10K")
      (footprint "RESC1609X55X30ML15T15")
      (description "SMD Chip Resistor, 1.67 kohm, ± 1%, 100 mW, 0603 [1608 Metric], Thick Film, Precision")
      (libsource (lib "Nebraska Instruments") (part "RES-2"))
    )
    (comp (ref "R24")
      (value "0603_10K")
      (footprint "RESC1609X55X30ML15T15")
      (description "SMD Chip Resistor, 1.67 kohm, ± 1%, 100 mW, 0603 [1608 Metric], Thick Film, Precision")
      (libsource (lib "Nebraska Instruments") (part "RES-2"))
    )
    (comp (ref "R25")
      (value "0603_0ohm")
      (footprint "RESC1609X55X30ML15T15")
      (description "SMD Chip Resistor, 0ohm, ± 1%, 100 mW, 0603 [1608 Metric], Thick Film, Precision")
      (libsource (lib "") (part "RES-2_1"))
    )
    (comp (ref "R26")
      (value "ERJ8BQFR30V")
      (footprint "RESC3216X70X50LL05T20")
      (fields (field (name "MANUFACTURER") "Panasonic"))
      (libsource (lib "Altium Content Vault") (part "RES"))
    )
    (comp (ref "R27")
      (value "0603_0ohm")
      (footprint "RESC1609X55X30ML15T15")
      (description "SMD Chip Resistor, 0ohm, ± 1%, 100 mW, 0603 [1608 Metric], Thick Film, Precision")
      (libsource (lib "") (part "RES-2_1"))
    )
    (comp (ref "R28")
      (value "0603_0ohm")
      (footprint "RESC1609X55X30ML15T15")
      (description "SMD Chip Resistor, 0ohm, ± 1%, 100 mW, 0603 [1608 Metric], Thick Film, Precision")
      (libsource (lib "") (part "RES-2_1"))
    )
    (comp (ref "R29")
      (value "ERJ3EKF1002V")
      (footprint "RESC1609X55X30LL15T15")
      (description "Chip Resistor, 10 KOhm, +/- 1%, 0.1 W, -55 to 155 degC, 0603 (1608 Metric), RoHS, Tape and Reel")
      (fields
        (field (name "RESISTANCE") "0")
        (field (name "TOLERANCE") "1%")
        (field (name "MANUFACTURER") "Panasonic")
      )
      (libsource (lib "Altium Content Vault") (part "RES-2"))
    )
    (comp (ref "R30")
      (value "ERJ3EKF1002V")
      (footprint "RESC1609X55X30LL15T15")
      (description "Chip Resistor, 10 KOhm, +/- 1%, 0.1 W, -55 to 155 degC, 0603 (1608 Metric), RoHS, Tape and Reel")
      (fields
        (field (name "RESISTANCE") "0")
        (field (name "TOLERANCE") "1%")
        (field (name "MANUFACTURER") "Panasonic")
      )
      (libsource (lib "Altium Content Vault") (part "RES-2"))
    )
    (comp (ref "R31")
      (value "ERJ3EKF1002V")
      (footprint "RESC1609X55X30LL15T15")
      (description "Chip Resistor, 10 KOhm, +/- 1%, 0.1 W, -55 to 155 degC, 0603 (1608 Metric), RoHS, Tape and Reel")
      (fields
        (field (name "RESISTANCE") "120")
        (field (name "TOLERANCE") "1%")
        (field (name "MANUFACTURER") "Panasonic")
      )
      (libsource (lib "Altium Content Vault") (part "RES-2"))
    )
    (comp (ref "R32")
      (value "ERJ3EKF1002V")
      (footprint "RESC1609X55X30LL15T15")
      (description "Chip Resistor, 10 KOhm, +/- 1%, 0.1 W, -55 to 155 degC, 0603 (1608 Metric), RoHS, Tape and Reel")
      (fields
        (field (name "RESISTANCE") "22")
        (field (name "TOLERANCE") "1%")
        (field (name "MANUFACTURER") "Panasonic")
      )
      (libsource (lib "Altium Content Vault") (part "RES-2"))
    )
    (comp (ref "R33")
      (value "ERJ3EKF1002V")
      (footprint "RESC1609X55X30LL15T15")
      (description "Chip Resistor, 10 KOhm, +/- 1%, 0.1 W, -55 to 155 degC, 0603 (1608 Metric), RoHS, Tape and Reel")
      (fields
        (field (name "RESISTANCE") "22")
        (field (name "TOLERANCE") "1%")
        (field (name "MANUFACTURER") "Panasonic")
      )
      (libsource (lib "Altium Content Vault") (part "RES-2"))
    )
    (comp (ref "R34")
      (value "0603_12K")
      (footprint "RESC1609X55X30ML15T15")
      (description "SMD Chip Resistor, 12 kohm, ± 1%, 100 mW, 0603 [1608 Metric], Thick Film, Precision")
      (libsource (lib "") (part "RES-2_5"))
    )
    (comp (ref "R35")
      (value "0603_1K")
      (footprint "RESC1609X55X30ML15T15")
      (description "SMD Chip Resistor, 1 kohm, ± 1%, 100 mW, 0603 [1608 Metric], Thick Film, Precision")
      (libsource (lib "") (part "RES-2_4"))
    )
    (comp (ref "R36")
      (value "0603_12K")
      (footprint "RESC1609X55X30ML15T15")
      (description "SMD Chip Resistor, 12 kohm, ± 1%, 100 mW, 0603 [1608 Metric], Thick Film, Precision")
      (libsource (lib "") (part "RES-2_5"))
    )
    (comp (ref "R37")
      (value "1.5K")
      (footprint "RESC1608X55X25ML10T15")
      (description "Chip Resistor, 10 KOhm, +/- 1%, 01 W, -55 to 155 degC, 0603 (1608 Metric)")
      (fields (field (name "POWER") "100mW") (field (name "TOLERANCE") "1%"))
      (libsource (lib "") (part "RES-2_3"))
    )
    (comp (ref "R38")
      (value "0603_1K")
      (footprint "RESC1609X55X30ML15T15")
      (description "SMD Chip Resistor, 1 kohm, ± 1%, 100 mW, 0603 [1608 Metric], Thick Film, Precision")
      (libsource (lib "") (part "RES-2_4"))
    )
    (comp (ref "R39")
      (value "0603_1K")
      (footprint "RESC1609X55X30ML15T15")
      (description "SMD Chip Resistor, 1 kohm, ± 1%, 100 mW, 0603 [1608 Metric], Thick Film, Precision")
      (libsource (lib "") (part "RES-2_4"))
    )
    (comp (ref "SW1")
      (value "PTS636 SKG25 SMTR LFS")
      (footprint "FP-PTS636_SKG25_SMTR_LFS-MFG")
      (description "TACT 6.0 X 3.5, 2.5 MM H, 250GF,")
      (libsource (lib "Altium Content Vault") (part "bdfe703aeb3461bf7c331fe9d798369"))
    )
    (comp (ref "TP1")
      (value "5019")
      (footprint "KSTN-5019_V")
      (description "Test Point, 1 Position SMD, RoHS, Tape and Reel")
      (libsource (lib "Altium Content Vault") (part "TESTPOINT_WHITE"))
    )
    (comp (ref "U1")
      (value "STM32F103C8T6")
      (footprint "STM-LQFP48_M")
      (description "IC MCU 32BIT 64KB FLASH 48LQFP")
      (libsource (lib "Nebraska Instruments") (part "MC-ARM-STM32F103X8_B-SQ48"))
    )
    (comp (ref "U2")
      (value "VN7003AHTR")
      (footprint "FP-Octapak-GAPGCFT00665-IPC_A")
      (description "High-side driver with Current Sense analog feedback for automotive applications")
      (libsource (lib "Nebraska Instruments") (part "74da48984cca5074ca4d2ff6f304a83"))
    )
    (comp (ref "U3")
      (value "SN65HVD230DR")
      (footprint "FP-D0008A-IPC_A")
      (description "IC TRANSCEIVER HALF 1/1 8SOIC")
      (libsource (lib "Altium Content Vault") (part "43b56812b1adf0e60a7acfb7c27ab91"))
    )
    (comp (ref "Y1")
      (value "ABM8G-16.000MHZ-18-D2Y-T")
      (footprint "FP-ABM8G-MFG")
      (description "Crystal 16MHz ±20ppm (Tol) ±30ppm (Stability) 18pF FUND 80Ω 4-Pin SMD T/R")
      (fields (field (name "TOLERANCE") "20ppm"))
      (libsource (lib "Altium Content Vault") (part "48e526d86b7f2615d98721063c72f49"))
    )
  )
  (nets
    (net (code "1") (name "/5VUSB") (class "Default")
      (node (ref "D2") (pin "1") (pinfunction "A1_1") (pintype "passive"))
      (node (ref "J6") (pin "1") (pinfunction "VBUS_1") (pintype "passive"))
    )
    (net (code "2") (name "/BACKUP_A") (class "Default")
      (node (ref "LED9") (pin "1") (pinfunction "A_1") (pintype "passive"))
      (node (ref "R4") (pin "1") (pinfunction "1_1") (pintype "passive"))
    )
    (net (code "3") (name "/BACKUP_C") (class "Default")
      (node (ref "IC2") (pin "7") (pinfunction "LC_7") (pintype "passive"))
      (node (ref "LED16") (pin "2") (pinfunction "K_2") (pintype "passive"))
    )
    (net (code "4") (name "/BACKUP_EN") (class "Default")
      (node (ref "P1") (pin "4") (pinfunction "4_4") (pintype "passive"))
      (node (ref "R17") (pin "1") (pinfunction "1_1") (pintype "passive"))
      (node (ref "U1") (pin "19") (pinfunction "PB1_19") (pintype "bidirectional"))
    )
    (net (code "5") (name "/BLU") (class "Default")
      (node (ref "LED28") (pin "4") (pinfunction "BLUE_ANODE_4") (pintype "passive"))
      (node (ref "U1") (pin "22") (pinfunction "PB11_22") (pintype "bidirectional"))
    )
    (net (code "6") (name "/BOOT0") (class "Default")
      (node (ref "R10") (pin "1") (pinfunction "1_1") (pintype "passive"))
      (node (ref "R11") (pin "2") (pinfunction "2_2") (pintype "passive"))
      (node (ref "U1") (pin "44") (pinfunction "BOOT0_44") (pintype "input"))
    )
    (net (code "7") (name "/BRAKE_A") (class "Default")
      (node (ref "LED29") (pin "1") (pinfunction "A_1") (pintype "passive"))
      (node (ref "R21") (pin "1") (pinfunction "1_1") (pintype "passive"))
    )
    (net (code "8") (name "/BRAKE_C") (class "Default")
      (node (ref "IC5") (pin "7") (pinfunction "LC_7") (pintype "passive"))
      (node (ref "LED8") (pin "2") (pinfunction "K_2") (pintype "passive"))
    )
    (net (code "9") (name "/BRAKE_EN") (class "Default")
      (node (ref "P1") (pin "3") (pinfunction "3_3") (pintype "passive"))
      (node (ref "R19") (pin "1") (pinfunction "1_1") (pintype "passive"))
      (node (ref "U1") (pin "18") (pinfunction "PB0_18") (pintype "bidirectional"))
    )
    (net (code "10") (name "/CAN_H") (class "Default")
      (node (ref "J5") (pin "1") (pinfunction "1_1") (pintype "passive"))
      (node (ref "P1") (pin "6") (pinfunction "6_6") (pintype "passive"))
      (node (ref "R31") (pin "2") (pinfunction "2_2") (pintype "passive"))
      (node (ref "U3") (pin "7") (pinfunction "CANH_7") (pintype "bidirectional"))
    )
    (net (code "11") (name "/CAN_L") (class "Default")
      (node (ref "J5") (pin "2") (pinfunction "2_2") (pintype "passive"))
      (node (ref "P1") (pin "5") (pinfunction "5_5") (pintype "passive"))
      (node (ref "R31") (pin "1") (pinfunction "1_1") (pintype "passive"))
      (node (ref "U3") (pin "6") (pinfunction "CANL_6") (pintype "bidirectional"))
    )
    (net (code "12") (name "/CAN_RX") (class "Default")
      (node (ref "R30") (pin "2") (pinfunction "2_2") (pintype "passive"))
      (node (ref "U1") (pin "45") (pinfunction "PB8_45") (pintype "bidirectional"))
    )
    (net (code "13") (name "/CAN_TX") (class "Default")
      (node (ref "R29") (pin "2") (pinfunction "2_2") (pintype "passive"))
      (node (ref "U1") (pin "46") (pinfunction "PB9_46") (pintype "bidirectional"))
    )
    (net (code "14") (name "/EXT_SW") (class "Default")
      (node (ref "P1") (pin "2") (pinfunction "2_2") (pintype "passive"))
      (node (ref "U1") (pin "16") (pinfunction "PA6_16") (pintype "bidirectional"))
      (node (ref "U2") (pin "4") (pinfunction "INPUT_4") (pintype "input"))
    )
    (net (code "15") (name "/GRN") (class "Default")
      (node (ref "LED28") (pin "5") (pinfunction "GREEN_ANODE_5") (pintype "passive"))
      (node (ref "U1") (pin "21") (pinfunction "PB10_21") (pintype "bidirectional"))
    )
    (net (code "16") (name "/MARKER_A") (class "Default")
      (node (ref "IC1") (pin "6") (pinfunction "LA_6") (pintype "output"))
      (node (ref "LED19") (pin "1") (pinfunction "A_1") (pintype "passive"))
    )
    (net (code "17") (name "/MARKER_C") (class "Default")
      (node (ref "IC1") (pin "7") (pinfunction "LC_7") (pintype "passive"))
      (node (ref "LED18") (pin "2") (pinfunction "K_2") (pintype "passive"))
    )
    (net (code "18") (name "/NRST") (class "Default")
      (node (ref "C4") (pin "2") (pinfunction "2_2") (pintype "passive"))
      (node (ref "J4") (pin "5") (pinfunction "5_5") (pintype "passive"))
      (node (ref "R6") (pin "1") (pinfunction "1_1") (pintype "passive"))
      (node (ref "SW1") (pin "1") (pinfunction "1_1") (pintype "passive"))
      (node (ref "U1") (pin "7") (pinfunction "NRST_7") (pintype "bidirectional"))
    )
    (net (code "19") (name "/RED") (class "Default")
      (node (ref "LED28") (pin "6") (pinfunction "RED_ANODE_6") (pintype "passive"))
      (node (ref "U1") (pin "20") (pinfunction "PB2_20") (pintype "bidirectional"))
    )
    (net (code "20") (name "/SWCLK") (class "Default")
      (node (ref "J4") (pin "2") (pinfunction "2_2") (pintype "passive"))
      (node (ref "U1") (pin "37") (pinfunction "PA14_37") (pintype "bidirectional"))
    )
    (net (code "21") (name "/SWDIO") (class "Default")
      (node (ref "J4") (pin "3") (pinfunction "3_3") (pintype "passive"))
      (node (ref "U1") (pin "34") (pinfunction "PA13_34") (pintype "bidirectional"))
    )
    (net (code "22") (name "/SW_CS") (class "Default")
      (node (ref "R36") (pin "1") (pinfunction "1_1") (pintype "passive"))
      (node (ref "U1") (pin "17") (pinfunction "PA7_17") (pintype "bidirectional"))
    )
    (net (code "23") (name "/TRACE") (class "Default")
      (node (ref "J4") (pin "4") (pinfunction "4_4") (pintype "passive"))
      (node (ref "U1") (pin "39") (pinfunction "PB3_39") (pintype "bidirectional"))
    )
    (net (code "24") (name "/TURN_EN") (class "Default")
      (node (ref "P1") (pin "7") (pinfunction "7_7") (pintype "passive"))
      (node (ref "R39") (pin "2") (pinfunction "2_2") (pintype "passive"))
    )
    (net (code "25") (name "/USB_DN") (class "Default")
      (node (ref "R32") (pin "1") (pinfunction "1_1") (pintype "passive"))
      (node (ref "U1") (pin "32") (pinfunction "PA11_32") (pintype "bidirectional"))
    )
    (net (code "26") (name "/USB_DP") (class "Default")
      (node (ref "R33") (pin "1") (pinfunction "1_1") (pintype "passive"))
      (node (ref "R37") (pin "2") (pinfunction "2_2") (pintype "passive"))
      (node (ref "U1") (pin "33") (pinfunction "PA12_33") (pintype "bidirectional"))
    )
    (net (code "27") (name "/VLED_EN") (class "Default")
      (node (ref "IC3") (pin "4") (pinfunction "EN_4") (pintype "passive"))
      (node (ref "R13") (pin "1") (pinfunction "1_1") (pintype "passive"))
      (node (ref "R38") (pin "2") (pinfunction "2_2") (pintype "passive"))
    )
    (net (code "28") (name "3V3") (class "Default")
      (node (ref "C1") (pin "2") (pinfunction "2_2") (pintype "passive"))
      (node (ref "C15") (pin "1") (pinfunction "1_1") (pintype "passive"))
      (node (ref "C17") (pin "2") (pinfunction "2_2") (pintype "passive"))
      (node (ref "C18") (pin "2") (pinfunction "2_2") (pintype "passive"))
      (node (ref "C2") (pin "2") (pinfunction "2_2") (pintype "passive"))
      (node (ref "C3") (pin "2") (pinfunction "2_2") (pintype "passive"))
      (node (ref "C7") (pin "2") (pinfunction "2_2") (pintype "passive"))
      (node (ref "C8") (pin "2") (pinfunction "2_2") (pintype "passive"))
      (node (ref "IC4") (pin "3") (pinfunction "VOUT_3") (pintype "passive"))
      (node (ref "R10") (pin "2") (pinfunction "2_2") (pintype "passive"))
      (node (ref "R37") (pin "1") (pinfunction "1_1") (pintype "passive"))
      (node (ref "R6") (pin "2") (pinfunction "2_2") (pintype "passive"))
      (node (ref "U1") (pin "1") (pinfunction "VBAT_1") (pintype "power_in"))
      (node (ref "U1") (pin "24") (pinfunction "VDD_1_24") (pintype "power_in"))
      (node (ref "U1") (pin "36") (pinfunction "VDD_2_36") (pintype "power_in"))
      (node (ref "U1") (pin "48") (pinfunction "VDD_3_48") (pintype "power_in"))
      (node (ref "U1") (pin "9") (pinfunction "VDDA_9") (pintype "power_in"))
      (node (ref "U3") (pin "3") (pinfunction "VCC_3") (pintype "power_in"))
    )
    (net (code "29") (name "12V") (class "Default")
      (node (ref "C13") (pin "2") (pinfunction "2_2") (pintype "passive"))
      (node (ref "C9") (pin "2") (pinfunction "2_2") (pintype "passive"))
      (node (ref "D2") (pin "2") (pinfunction "A2_2") (pintype "passive"))
      (node (ref "IC3") (pin "3") (pinfunction "VIN_3") (pintype "passive"))
      (node (ref "L1") (pin "1") (pinfunction "1_1") (pintype "passive"))
      (node (ref "P1") (pin "1") (pinfunction "1_1") (pintype "passive"))
      (node (ref "R13") (pin "2") (pinfunction "2_2") (pintype "passive"))
      (node (ref "R28") (pin "2") (pinfunction "2_2") (pintype "passive"))
    )
    (net (code "30") (name "GND") (class "Default")
      (node (ref "C1") (pin "1") (pinfunction "1_1") (pintype "passive"))
      (node (ref "C10") (pin "1") (pinfunction "1_1") (pintype "passive"))
      (node (ref "C11") (pin "1") (pinfunction "1_1") (pintype "passive"))
      (node (ref "C12") (pin "1") (pinfunction "1_1") (pintype "passive"))
      (node (ref "C13") (pin "1") (pinfunction "1_1") (pintype "passive"))
      (node (ref "C14") (pin "1") (pinfunction "1_1") (pintype "passive"))
      (node (ref "C15") (pin "2") (pinfunction "2_2") (pintype "passive"))
      (node (ref "C16") (pin "2") (pinfunction "2_2") (pintype "passive"))
      (node (ref "C17") (pin "1") (pinfunction "1_1") (pintype "passive"))
      (node (ref "C18") (pin "1") (pinfunction "1_1") (pintype "passive"))
      (node (ref "C19") (pin "2") (pinfunction "2_2") (pintype "passive"))
      (node (ref "C2") (pin "1") (pinfunction "1_1") (pintype "passive"))
      (node (ref "C20") (pin "2") (pinfunction "2_2") (pintype "passive"))
      (node (ref "C3") (pin "1") (pinfunction "1_1") (pintype "passive"))
      (node (ref "C4") (pin "1") (pinfunction "1_1") (pintype "passive"))
      (node (ref "C5") (pin "1") (pinfunction "1_1") (pintype "passive"))
      (node (ref "C6") (pin "1") (pinfunction "1_1") (pintype "passive"))
      (node (ref "C7") (pin "1") (pinfunction "1_1") (pintype "passive"))
      (node (ref "C8") (pin "1") (pinfunction "1_1") (pintype "passive"))
      (node (ref "C9") (pin "1") (pinfunction "1_1") (pintype "passive"))
      (node (ref "D3") (pin "2") (pinfunction "A_2") (pintype "passive"))
      (node (ref "IC1") (pin "2") (pinfunction "GND_2") (pintype "power_in"))
      (node (ref "IC1") (pin "9") (pinfunction "PAD_9") (pintype "passive"))
      (node (ref "IC2") (pin "2") (pinfunction "GND_2") (pintype "power_in"))
      (node (ref "IC2") (pin "9") (pinfunction "PAD_9") (pintype "passive"))
      (node (ref "IC3") (pin "11") (pinfunction "NC_11") (pintype "passive"))
      (node (ref "IC3") (pin "12") (pinfunction "PGND_1_12") (pintype "passive"))
      (node (ref "IC3") (pin "13") (pinfunction "PGND_2_13") (pintype "passive"))
      (node (ref "IC3") (pin "14") (pinfunction "PGND_3_14") (pintype "passive"))
      (node (ref "IC3") (pin "15") (pinfunction "EP_15") (pintype "passive"))
      (node (ref "IC3") (pin "6") (pinfunction "SYNC_6") (pintype "passive"))
      (node (ref "IC3") (pin "7") (pinfunction "AGND_7") (pintype "passive"))
      (node (ref "IC4") (pin "2") (pinfunction "GND_1_2") (pintype "passive"))
      (node (ref "IC4") (pin "4") (pinfunction "GND_2_4") (pintype "passive"))
      (node (ref "IC5") (pin "2") (pinfunction "GND_2") (pintype "power_in"))
      (node (ref "IC5") (pin "9") (pinfunction "PAD_9") (pintype "passive"))
      (node (ref "IC6") (pin "2") (pinfunction "GND_2") (pintype "power_in"))
      (node (ref "IC6") (pin "9") (pinfunction "PAD_9") (pintype "passive"))
      (node (ref "J1") (pin "2") (pinfunction "2_2") (pintype "passive"))
      (node (ref "J2") (pin "2") (pinfunction "2_2") (pintype "passive"))
      (node (ref "J3") (pin "2") (pinfunction "2_2") (pintype "passive"))
      (node (ref "J4") (pin "6") (pinfunction "6_6") (pintype "passive"))
      (node (ref "J6") (pin "5") (pinfunction "GND_5") (pintype "passive"))
      (node (ref "LED10") (pin "3") (pinfunction "EP_3") (pintype "passive"))
      (node (ref "LED11") (pin "3") (pinfunction "EP_3") (pintype "passive"))
      (node (ref "LED12") (pin "3") (pinfunction "EP_3") (pintype "passive"))
      (node (ref "LED13") (pin "3") (pinfunction "EP_3") (pintype "passive"))
      (node (ref "LED14") (pin "3") (pinfunction "EP_3") (pintype "passive"))
      (node (ref "LED15") (pin "3") (pinfunction "EP_3") (pintype "passive"))
      (node (ref "LED16") (pin "3") (pinfunction "EP_3") (pintype "passive"))
      (node (ref "LED17") (pin "3") (pinfunction "EP_3") (pintype "passive"))
      (node (ref "LED18") (pin "3") (pinfunction "EP_3") (pintype "passive"))
      (node (ref "LED19") (pin "3") (pinfunction "EP_3") (pintype "passive"))
      (node (ref "LED9") (pin "3") (pinfunction "EP_3") (pintype "passive"))
      (node (ref "P1") (pin "8") (pinfunction "8_8") (pintype "passive"))
      (node (ref "R11") (pin "1") (pinfunction "1_1") (pintype "passive"))
      (node (ref "R12") (pin "1") (pinfunction "1_1") (pintype "passive"))
      (node (ref "R16") (pin "1") (pinfunction "1_1") (pintype "passive"))
      (node (ref "R18") (pin "1") (pinfunction "1_1") (pintype "passive"))
      (node (ref "R2") (pin "1") (pinfunction "1_1") (pintype "passive"))
      (node (ref "R20") (pin "1") (pinfunction "1_1") (pintype "passive"))
      (node (ref "R22") (pin "1") (pinfunction "1_1") (pintype "passive"))
      (node (ref "R24") (pin "1") (pinfunction "1_1") (pintype "passive"))
      (node (ref "R26") (pin "1") (pinfunction "1_1") (pintype "passive"))
      (node (ref "R34") (pin "1") (pinfunction "1_1") (pintype "passive"))
      (node (ref "R35") (pin "2") (pinfunction "2_2") (pintype "passive"))
      (node (ref "R5") (pin "1") (pinfunction "1_1") (pintype "passive"))
      (node (ref "R7") (pin "2") (pinfunction "2_2") (pintype "passive"))
      (node (ref "R8") (pin "2") (pinfunction "2_2") (pintype "passive"))
      (node (ref "R9") (pin "2") (pinfunction "2_2") (pintype "passive"))
      (node (ref "SW1") (pin "2") (pinfunction "2_2") (pintype "passive"))
      (node (ref "U1") (pin "23") (pinfunction "VSS_1_23") (pintype "power_in"))
      (node (ref "U1") (pin "35") (pinfunction "VSS_2_35") (pintype "power_in"))
      (node (ref "U1") (pin "47") (pinfunction "VSS_3_47") (pintype "power_in"))
      (node (ref "U1") (pin "8") (pinfunction "VSSA_8") (pintype "power_in"))
      (node (ref "U2") (pin "7") (pinfunction "GND_7") (pintype "power_in"))
      (node (ref "U3") (pin "2") (pinfunction "GND_2") (pintype "power_in"))
      (node (ref "U3") (pin "8") (pinfunction "RS_8") (pintype "input"))
      (node (ref "Y1") (pin "2") (pinfunction "GND_2") (pintype "power_in"))
      (node (ref "Y1") (pin "4") (pinfunction "GND_4") (pintype "power_in"))
    )
    (net (code "31") (name "Net-(C11-Pad2)") (class "Default")
      (node (ref "C11") (pin "2") (pinfunction "2_2") (pintype "passive"))
      (node (ref "R14") (pin "1") (pinfunction "1_1") (pintype "passive"))
    )
    (net (code "32") (name "Net-(D1-A)") (class "Default")
      (node (ref "D1") (pin "1") (pinfunction "A_1") (pintype "passive"))
      (node (ref "IC3") (pin "1") (pinfunction "SW_1_1") (pintype "passive"))
      (node (ref "IC3") (pin "2") (pinfunction "SW_2_2") (pintype "passive"))
      (node (ref "L1") (pin "2") (pinfunction "2_2") (pintype "passive"))
    )
    (net (code "33") (name "Net-(D2-K)") (class "Default")
      (node (ref "C5") (pin "2") (pinfunction "2_2") (pintype "passive"))
      (node (ref "C6") (pin "2") (pinfunction "2_2") (pintype "passive"))
      (node (ref "D2") (pin "3") (pinfunction "K_3") (pintype "passive"))
      (node (ref "IC4") (pin "1") (pinfunction "VIN_1") (pintype "passive"))
    )
    (net (code "34") (name "Net-(D3-K)") (class "Default")
      (node (ref "D3") (pin "1") (pinfunction "K_1") (pintype "passive"))
      (node (ref "R39") (pin "1") (pinfunction "1_1") (pintype "passive"))
      (node (ref "U1") (pin "42") (pinfunction "PB6_42") (pintype "bidirectional"))
    )
    (net (code "35") (name "Net-(IC1-EN)") (class "Default")
      (node (ref "IC1") (pin "4") (pinfunction "EN_4") (pintype "passive"))
      (node (ref "R1") (pin "1") (pinfunction "1_1") (pintype "passive"))
      (node (ref "TP1") (pin "1") (pinfunction "1_1") (pintype "passive"))
    )
    (net (code "36") (name "Net-(IC1-LSS)") (class "Default")
      (node (ref "IC1") (pin "1") (pinfunction "SENSE_1") (pintype "passive"))
      (node (ref "IC1") (pin "8") (pinfunction "LSS_8") (pintype "passive"))
      (node (ref "R2") (pin "2") (pinfunction "2_2") (pintype "passive"))
    )
    (net (code "37") (name "Net-(IC1-VIN)") (class "Default")
      (node (ref "IC1") (pin "5") (pinfunction "VIN_5") (pintype "power_in"))
      (node (ref "J1") (pin "1") (pinfunction "1_1") (pintype "passive"))
      (node (ref "R1") (pin "2") (pinfunction "2_2") (pintype "passive"))
    )
    (net (code "38") (name "Net-(IC2-EN)") (class "Default")
      (node (ref "IC2") (pin "4") (pinfunction "EN_4") (pintype "passive"))
      (node (ref "R17") (pin "2") (pinfunction "2_2") (pintype "passive"))
    )
    (net (code "39") (name "Net-(IC2-LA)") (class "Default")
      (node (ref "IC2") (pin "6") (pinfunction "LA_6") (pintype "output"))
      (node (ref "R4") (pin "2") (pinfunction "2_2") (pintype "passive"))
    )
    (net (code "40") (name "Net-(IC2-LSS)") (class "Default")
      (node (ref "IC2") (pin "1") (pinfunction "SENSE_1") (pintype "passive"))
      (node (ref "IC2") (pin "8") (pinfunction "LSS_8") (pintype "passive"))
      (node (ref "R5") (pin "2") (pinfunction "2_2") (pintype "passive"))
    )
    (net (code "41") (name "Net-(IC2-THTH)") (class "Default")
      (node (ref "IC2") (pin "3") (pinfunction "THTH_3") (pintype "passive"))
      (node (ref "R18") (pin "2") (pinfunction "2_2") (pintype "passive"))
    )
    (net (code "42") (name "Net-(IC3-COMP)") (class "Default")
      (node (ref "IC3") (pin "8") (pinfunction "COMP_8") (pintype "passive"))
      (node (ref "R14") (pin "2") (pinfunction "2_2") (pintype "passive"))
    )
    (net (code "43") (name "Net-(IC3-FB)") (class "Default")
      (node (ref "IC3") (pin "9") (pinfunction "FB_9") (pintype "passive"))
      (node (ref "R15") (pin "1") (pinfunction "1_1") (pintype "passive"))
      (node (ref "R16") (pin "2") (pinfunction "2_2") (pintype "passive"))
    )
    (net (code "44") (name "Net-(IC3-FREQ)") (class "Default")
      (node (ref "IC3") (pin "10") (pinfunction "FREQ_10") (pintype "passive"))
      (node (ref "R12") (pin "2") (pinfunction "2_2") (pintype "passive"))
    )
    (net (code "45") (name "Net-(IC3-SS)") (class "Default")
      (node (ref "C10") (pin "2") (pinfunction "2_2") (pintype "passive"))
      (node (ref "IC3") (pin "5") (pinfunction "SS_5") (pintype "passive"))
    )
    (net (code "46") (name "Net-(IC5-EN)") (class "Default")
      (node (ref "IC5") (pin "4") (pinfunction "EN_4") (pintype "passive"))
      (node (ref "R19") (pin "2") (pinfunction "2_2") (pintype "passive"))
    )
    (net (code "47") (name "Net-(IC5-LA)") (class "Default")
      (node (ref "IC5") (pin "6") (pinfunction "LA_6") (pintype "output"))
      (node (ref "R21") (pin "2") (pinfunction "2_2") (pintype "passive"))
    )
    (net (code "48") (name "Net-(IC5-LSS)") (class "Default")
      (node (ref "IC5") (pin "1") (pinfunction "SENSE_1") (pintype "passive"))
      (node (ref "IC5") (pin "8") (pinfunction "LSS_8") (pintype "passive"))
      (node (ref "R22") (pin "2") (pinfunction "2_2") (pintype "passive"))
    )
    (net (code "49") (name "Net-(IC5-THTH)") (class "Default")
      (node (ref "IC5") (pin "3") (pinfunction "THTH_3") (pintype "passive"))
      (node (ref "R20") (pin "2") (pinfunction "2_2") (pintype "passive"))
    )
    (net (code "50") (name "Net-(IC6-EN)") (class "Default")
      (node (ref "IC6") (pin "4") (pinfunction "EN_4") (pintype "passive"))
      (node (ref "R23") (pin "2") (pinfunction "2_2") (pintype "passive"))
    )
    (net (code "51") (name "Net-(IC6-LA)") (class "Default")
      (node (ref "IC6") (pin "6") (pinfunction "LA_6") (pintype "output"))
      (node (ref "R25") (pin "2") (pinfunction "2_2") (pintype "passive"))
    )
    (net (code "52") (name "Net-(IC6-LC)") (class "Default")
      (node (ref "IC6") (pin "7") (pinfunction "LC_7") (pintype "passive"))
      (node (ref "LED27") (pin "2") (pinfunction "K_2") (pintype "passive"))
    )
    (net (code "53") (name "Net-(IC6-LSS)") (class "Default")
      (node (ref "IC6") (pin "1") (pinfunction "SENSE_1") (pintype "passive"))
      (node (ref "IC6") (pin "8") (pinfunction "LSS_8") (pintype "passive"))
      (node (ref "R26") (pin "2") (pinfunction "2_2") (pintype "passive"))
    )
    (net (code "54") (name "Net-(IC6-THTH)") (class "Default")
      (node (ref "IC6") (pin "3") (pinfunction "THTH_3") (pintype "passive"))
      (node (ref "R24") (pin "2") (pinfunction "2_2") (pintype "passive"))
    )
    (net (code "55") (name "Net-(IC6-VIN)") (class "Default")
      (node (ref "IC6") (pin "5") (pinfunction "VIN_5") (pintype "power_in"))
      (node (ref "J2") (pin "1") (pinfunction "1_1") (pintype "passive"))
      (node (ref "R23") (pin "1") (pinfunction "1_1") (pintype "passive"))
    )
    (net (code "56") (name "Net-(J3-Pad1)") (class "Default")
      (node (ref "J3") (pin "1") (pinfunction "1_1") (pintype "passive"))
      (node (ref "U2") (pin "1") (pinfunction "OUTPUT_1") (pintype "output"))
      (node (ref "U2") (pin "2") (pinfunction "OUTPUT_2") (pintype "output"))
      (node (ref "U2") (pin "3") (pinfunction "OUTPUT_3") (pintype "output"))
    )
    (net (code "57") (name "Net-(J6-D+)") (class "Default")
      (node (ref "J6") (pin "3") (pinfunction "D+_3") (pintype "passive"))
      (node (ref "R33") (pin "2") (pinfunction "2_2") (pintype "passive"))
    )
    (net (code "58") (name "Net-(J6-D-)") (class "Default")
      (node (ref "J6") (pin "2") (pinfunction "D-_2") (pintype "passive"))
      (node (ref "R32") (pin "2") (pinfunction "2_2") (pintype "passive"))
    )
    (net (code "59") (name "Net-(J6-SHLD1)") (class "Default")
      (node (ref "C19") (pin "1") (pinfunction "1_1") (pintype "passive"))
      (node (ref "J6") (pin "6") (pinfunction "SHLD1_6") (pintype "passive"))
      (node (ref "J6") (pin "7") (pinfunction "SHLD2_7") (pintype "passive"))
      (node (ref "J6") (pin "8") (pinfunction "SHLD3_8") (pintype "passive"))
      (node (ref "R35") (pin "1") (pinfunction "1_1") (pintype "passive"))
    )
    (net (code "60") (name "Net-(LED1-A)") (class "Default")
      (node (ref "LED1") (pin "1") (pinfunction "A_1") (pintype "passive"))
      (node (ref "LED36") (pin "2") (pinfunction "K_2") (pintype "passive"))
    )
    (net (code "61") (name "Net-(LED1-K)") (class "Default")
      (node (ref "LED1") (pin "2") (pinfunction "K_2") (pintype "passive"))
      (node (ref "LED2") (pin "1") (pinfunction "A_1") (pintype "passive"))
    )
    (net (code "62") (name "Net-(LED2-K)") (class "Default")
      (node (ref "LED2") (pin "2") (pinfunction "K_2") (pintype "passive"))
      (node (ref "LED3") (pin "1") (pinfunction "A_1") (pintype "passive"))
    )
    (net (code "63") (name "Net-(LED3-K)") (class "Default")
      (node (ref "LED3") (pin "2") (pinfunction "K_2") (pintype "passive"))
      (node (ref "LED4") (pin "1") (pinfunction "A_1") (pintype "passive"))
    )
    (net (code "64") (name "Net-(LED4-K)") (class "Default")
      (node (ref "LED4") (pin "2") (pinfunction "K_2") (pintype "passive"))
      (node (ref "LED5") (pin "1") (pinfunction "A_1") (pintype "passive"))
    )
    (net (code "65") (name "Net-(LED5-K)") (class "Default")
      (node (ref "LED5") (pin "2") (pinfunction "K_2") (pintype "passive"))
      (node (ref "LED6") (pin "1") (pinfunction "A_1") (pintype "passive"))
    )
    (net (code "66") (name "Net-(LED6-K)") (class "Default")
      (node (ref "LED6") (pin "2") (pinfunction "K_2") (pintype "passive"))
      (node (ref "LED7") (pin "1") (pinfunction "A_1") (pintype "passive"))
    )
    (net (code "67") (name "Net-(LED7-K)") (class "Default")
      (node (ref "LED7") (pin "2") (pinfunction "K_2") (pintype "passive"))
      (node (ref "LED8") (pin "1") (pinfunction "A_1") (pintype "passive"))
    )
    (net (code "68") (name "Net-(LED10-A)") (class "Default")
      (node (ref "LED10") (pin "1") (pinfunction "A_1") (pintype "passive"))
      (node (ref "LED9") (pin "2") (pinfunction "K_2") (pintype "passive"))
    )
    (net (code "69") (name "Net-(LED10-K)") (class "Default")
      (node (ref "LED10") (pin "2") (pinfunction "K_2") (pintype "passive"))
      (node (ref "LED11") (pin "1") (pinfunction "A_1") (pintype "passive"))
    )
    (net (code "70") (name "Net-(LED11-K)") (class "Default")
      (node (ref "LED11") (pin "2") (pinfunction "K_2") (pintype "passive"))
      (node (ref "LED12") (pin "1") (pinfunction "A_1") (pintype "passive"))
    )
    (net (code "71") (name "Net-(LED12-K)") (class "Default")
      (node (ref "LED12") (pin "2") (pinfunction "K_2") (pintype "passive"))
      (node (ref "LED13") (pin "1") (pinfunction "A_1") (pintype "passive"))
    )
    (net (code "72") (name "Net-(LED13-K)") (class "Default")
      (node (ref "LED13") (pin "2") (pinfunction "K_2") (pintype "passive"))
      (node (ref "LED14") (pin "1") (pinfunction "A_1") (pintype "passive"))
    )
    (net (code "73") (name "Net-(LED14-K)") (class "Default")
      (node (ref "LED14") (pin "2") (pinfunction "K_2") (pintype "passive"))
      (node (ref "LED15") (pin "1") (pinfunction "A_1") (pintype "passive"))
    )
    (net (code "74") (name "Net-(LED15-K)") (class "Default")
      (node (ref "LED15") (pin "2") (pinfunction "K_2") (pintype "passive"))
      (node (ref "LED16") (pin "1") (pinfunction "A_1") (pintype "passive"))
    )
    (net (code "75") (name "Net-(LED17-A)") (class "Default")
      (node (ref "LED17") (pin "1") (pinfunction "A_1") (pintype "passive"))
      (node (ref "LED19") (pin "2") (pinfunction "K_2") (pintype "passive"))
      (node (ref "R3") (pin "2") (pinfunction "2_2") (pintype "passive"))
    )
    (net (code "76") (name "Net-(LED17-K)") (class "Default")
      (node (ref "LED17") (pin "2") (pinfunction "K_2") (pintype "passive"))
      (node (ref "LED18") (pin "1") (pinfunction "A_1") (pintype "passive"))
      (node (ref "R3") (pin "1") (pinfunction "1_1") (pintype "passive"))
    )
    (net (code "77") (name "Net-(LED20-A)") (class "Default")
      (node (ref "LED20") (pin "1") (pinfunction "A_1") (pintype "passive"))
      (node (ref "R25") (pin "1") (pinfunction "1_1") (pintype "passive"))
    )
    (net (code "78") (name "Net-(LED20-K)") (class "Default")
      (node (ref "LED20") (pin "2") (pinfunction "K_2") (pintype "passive"))
      (node (ref "LED21") (pin "1") (pinfunction "A_1") (pintype "passive"))
    )
    (net (code "79") (name "Net-(LED21-K)") (class "Default")
      (node (ref "LED21") (pin "2") (pinfunction "K_2") (pintype "passive"))
      (node (ref "LED22") (pin "1") (pinfunction "A_1") (pintype "passive"))
    )
    (net (code "80") (name "Net-(LED22-K)") (class "Default")
      (node (ref "LED22") (pin "2") (pinfunction "K_2") (pintype "passive"))
      (node (ref "LED23") (pin "1") (pinfunction "A_1") (pintype "passive"))
    )
    (net (code "81") (name "Net-(LED23-K)") (class "Default")
      (node (ref "LED23") (pin "2") (pinfunction "K_2") (pintype "passive"))
      (node (ref "LED24") (pin "1") (pinfunction "A_1") (pintype "passive"))
    )
    (net (code "82") (name "Net-(LED24-K)") (class "Default")
      (node (ref "LED24") (pin "2") (pinfunction "K_2") (pintype "passive"))
      (node (ref "LED25") (pin "1") (pinfunction "A_1") (pintype "passive"))
    )
    (net (code "83") (name "Net-(LED25-K)") (class "Default")
      (node (ref "LED25") (pin "2") (pinfunction "K_2") (pintype "passive"))
      (node (ref "LED26") (pin "1") (pinfunction "A_1") (pintype "passive"))
    )
    (net (code "84") (name "Net-(LED26-K)") (class "Default")
      (node (ref "LED26") (pin "2") (pinfunction "K_2") (pintype "passive"))
      (node (ref "LED27") (pin "1") (pinfunction "A_1") (pintype "passive"))
    )
    (net (code "85") (name "Net-(LED28-BLUE_CATHODE)") (class "Default")
      (node (ref "LED28") (pin "3") (pinfunction "BLUE_CATHODE_3") (pintype "passive"))
      (node (ref "R9") (pin "1") (pinfunction "1_1") (pintype "passive"))
    )
    (net (code "86") (name "Net-(LED28-GREEN_CATHODE)") (class "Default")
      (node (ref "LED28") (pin "2") (pinfunction "GREEN_CATHODE_2") (pintype "passive"))
      (node (ref "R8") (pin "1") (pinfunction "1_1") (pintype "passive"))
    )
    (net (code "87") (name "Net-(LED28-RED_CATHODE)") (class "Default")
      (node (ref "LED28") (pin "1") (pinfunction "RED_CATHODE_1") (pintype "passive"))
      (node (ref "R7") (pin "1") (pinfunction "1_1") (pintype "passive"))
    )
    (net (code "88") (name "Net-(LED29-K)") (class "Default")
      (node (ref "LED29") (pin "2") (pinfunction "K_2") (pintype "passive"))
      (node (ref "LED30") (pin "1") (pinfunction "A_1") (pintype "passive"))
    )
    (net (code "89") (name "Net-(LED30-K)") (class "Default")
      (node (ref "LED30") (pin "2") (pinfunction "K_2") (pintype "passive"))
      (node (ref "LED31") (pin "1") (pinfunction "A_1") (pintype "passive"))
    )
    (net (code "90") (name "Net-(LED31-K)") (class "Default")
      (node (ref "LED31") (pin "2") (pinfunction "K_2") (pintype "passive"))
      (node (ref "LED32") (pin "1") (pinfunction "A_1") (pintype "passive"))
    )
    (net (code "91") (name "Net-(LED32-K)") (class "Default")
      (node (ref "LED32") (pin "2") (pinfunction "K_2") (pintype "passive"))
      (node (ref "LED33") (pin "1") (pinfunction "A_1") (pintype "passive"))
    )
    (net (code "92") (name "Net-(LED33-K)") (class "Default")
      (node (ref "LED33") (pin "2") (pinfunction "K_2") (pintype "passive"))
      (node (ref "LED34") (pin "1") (pinfunction "A_1") (pintype "passive"))
    )
    (net (code "93") (name "Net-(LED34-K)") (class "Default")
      (node (ref "LED34") (pin "2") (pinfunction "K_2") (pintype "passive"))
      (node (ref "LED35") (pin "1") (pinfunction "A_1") (pintype "passive"))
    )
    (net (code "94") (name "Net-(LED35-K)") (class "Default")
      (node (ref "LED35") (pin "2") (pinfunction "K_2") (pintype "passive"))
      (node (ref "LED36") (pin "1") (pinfunction "A_1") (pintype "passive"))
    )
    (net (code "95") (name "Net-(U1A-PB15)") (class "Default")
      (node (ref "R38") (pin "1") (pinfunction "1_1") (pintype "passive"))
      (node (ref "U1") (pin "28") (pinfunction "PB15_28") (pintype "bidirectional"))
    )
    (net (code "96") (name "Net-(U1A-PD0-OSC_IN)") (class "Default")
      (node (ref "C16") (pin "1") (pinfunction "1_1") (pintype "passive"))
      (node (ref "U1") (pin "5") (pinfunction "PD0-OSC_IN_5") (pintype "bidirectional"))
      (node (ref "Y1") (pin "3") (pinfunction "3_3") (pintype "passive"))
    )
    (net (code "97") (name "Net-(U1A-PD1-OSC_OUT)") (class "Default")
      (node (ref "C20") (pin "1") (pinfunction "1_1") (pintype "passive"))
      (node (ref "U1") (pin "6") (pinfunction "PD1-OSC_OUT_6") (pintype "bidirectional"))
      (node (ref "Y1") (pin "1") (pinfunction "1_1") (pintype "passive"))
    )
    (net (code "98") (name "Net-(U2-CS)") (class "Default")
      (node (ref "R34") (pin "2") (pinfunction "2_2") (pintype "passive"))
      (node (ref "R36") (pin "2") (pinfunction "2_2") (pintype "passive"))
      (node (ref "U2") (pin "5") (pinfunction "CS_5") (pintype "input"))
    )
    (net (code "99") (name "Net-(U2-VCC)") (class "Default")
      (node (ref "R27") (pin "1") (pinfunction "1_1") (pintype "passive"))
      (node (ref "R28") (pin "1") (pinfunction "1_1") (pintype "passive"))
      (node (ref "U2") (pin "8") (pinfunction "VCC_8") (pintype "power_in"))
    )
    (net (code "100") (name "Net-(U3-D)") (class "Default")
      (node (ref "R29") (pin "1") (pinfunction "1_1") (pintype "passive"))
      (node (ref "U3") (pin "1") (pinfunction "D_1") (pintype "input"))
    )
    (net (code "101") (name "Net-(U3-R)") (class "Default")
      (node (ref "R30") (pin "1") (pinfunction "1_1") (pintype "passive"))
      (node (ref "U3") (pin "4") (pinfunction "R_4") (pintype "output"))
    )
    (net (code "102") (name "Net-(U3-VREF)") (class "Default")
      (node (ref "CANR") (pin "1") (pinfunction "1_1") (pintype "passive"))
      (node (ref "U3") (pin "5") (pinfunction "VREF_5") (pintype "output"))
    )
    (net (code "103") (name "VLED") (class "Default")
      (node (ref "C12") (pin "2") (pinfunction "2_2") (pintype "passive"))
      (node (ref "C14") (pin "2") (pinfunction "2_2") (pintype "passive"))
      (node (ref "D1") (pin "2") (pinfunction "K_2") (pintype "passive"))
      (node (ref "IC2") (pin "5") (pinfunction "VIN_5") (pintype "power_in"))
      (node (ref "IC5") (pin "5") (pinfunction "VIN_5") (pintype "power_in"))
      (node (ref "R15") (pin "2") (pinfunction "2_2") (pintype "passive"))
      (node (ref "R27") (pin "2") (pinfunction "2_2") (pintype "passive"))
    )
    (net (code "104") (name "unconnected-(IC1-THTH-Pad3)") (class "Default")
      (node (ref "IC1") (pin "3") (pinfunction "THTH_3") (pintype "passive+no_connect"))
    )
    (net (code "105") (name "unconnected-(J4-Pad1)") (class "Default")
      (node (ref "J4") (pin "1") (pinfunction "1_1") (pintype "passive"))
    )
    (net (code "106") (name "unconnected-(J6-ID-Pad4)") (class "Default")
      (node (ref "J6") (pin "4") (pinfunction "ID_4") (pintype "passive+no_connect"))
    )
    (net (code "107") (name "unconnected-(P1-PadMH1)") (class "Default")
      (node (ref "P1") (pin "MH1") (pinfunction "MH1_MH1") (pintype "passive+no_connect"))
    )
    (net (code "108") (name "unconnected-(P1-PadMH2)") (class "Default")
      (node (ref "P1") (pin "MH2") (pinfunction "MH2_MH2") (pintype "passive+no_connect"))
    )
    (net (code "109") (name "unconnected-(SW1-GROUND-Pad3)") (class "Default")
      (node (ref "SW1") (pin "3") (pinfunction "GROUND_3") (pintype "power_in+no_connect"))
    )
    (net (code "110") (name "unconnected-(SW1-GROUND-Pad4)") (class "Default")
      (node (ref "SW1") (pin "4") (pinfunction "GROUND_4") (pintype "power_in+no_connect"))
    )
    (net (code "111") (name "unconnected-(U1A-PA0-WKUP-Pad10)") (class "Default")
      (node (ref "U1") (pin "10") (pinfunction "PA0-WKUP_10") (pintype "bidirectional"))
    )
    (net (code "112") (name "unconnected-(U1A-PA1-Pad11)") (class "Default")
      (node (ref "U1") (pin "11") (pinfunction "PA1_11") (pintype "bidirectional"))
    )
    (net (code "113") (name "unconnected-(U1A-PA2-Pad12)") (class "Default")
      (node (ref "U1") (pin "12") (pinfunction "PA2_12") (pintype "bidirectional"))
    )
    (net (code "114") (name "unconnected-(U1A-PA3-Pad13)") (class "Default")
      (node (ref "U1") (pin "13") (pinfunction "PA3_13") (pintype "bidirectional"))
    )
    (net (code "115") (name "unconnected-(U1A-PA4-Pad14)") (class "Default")
      (node (ref "U1") (pin "14") (pinfunction "PA4_14") (pintype "bidirectional"))
    )
    (net (code "116") (name "unconnected-(U1A-PA5-Pad15)") (class "Default")
      (node (ref "U1") (pin "15") (pinfunction "PA5_15") (pintype "bidirectional"))
    )
    (net (code "117") (name "unconnected-(U1A-PA8-Pad29)") (class "Default")
      (node (ref "U1") (pin "29") (pinfunction "PA8_29") (pintype "bidirectional"))
    )
    (net (code "118") (name "unconnected-(U1A-PA9-Pad30)") (class "Default")
      (node (ref "U1") (pin "30") (pinfunction "PA9_30") (pintype "bidirectional"))
    )
    (net (code "119") (name "unconnected-(U1A-PA10-Pad31)") (class "Default")
      (node (ref "U1") (pin "31") (pinfunction "PA10_31") (pintype "bidirectional"))
    )
    (net (code "120") (name "unconnected-(U1A-PA15-Pad38)") (class "Default")
      (node (ref "U1") (pin "38") (pinfunction "PA15_38") (pintype "bidirectional"))
    )
    (net (code "121") (name "unconnected-(U1A-PB4-Pad40)") (class "Default")
      (node (ref "U1") (pin "40") (pinfunction "PB4_40") (pintype "bidirectional"))
    )
    (net (code "122") (name "unconnected-(U1A-PB5-Pad41)") (class "Default")
      (node (ref "U1") (pin "41") (pinfunction "PB5_41") (pintype "bidirectional"))
    )
    (net (code "123") (name "unconnected-(U1A-PB7-Pad43)") (class "Default")
      (node (ref "U1") (pin "43") (pinfunction "PB7_43") (pintype "bidirectional"))
    )
    (net (code "124") (name "unconnected-(U1A-PB12-Pad25)") (class "Default")
      (node (ref "U1") (pin "25") (pinfunction "PB12_25") (pintype "bidirectional"))
    )
    (net (code "125") (name "unconnected-(U1A-PB13-Pad26)") (class "Default")
      (node (ref "U1") (pin "26") (pinfunction "PB13_26") (pintype "bidirectional"))
    )
    (net (code "126") (name "unconnected-(U1A-PB14-Pad27)") (class "Default")
      (node (ref "U1") (pin "27") (pinfunction "PB14_27") (pintype "bidirectional"))
    )
    (net (code "127") (name "unconnected-(U1A-PC13-TAMPER-RTC-Pad2)") (class "Default")
      (node (ref "U1") (pin "2") (pinfunction "PC13-TAMPER-RTC_2") (pintype "bidirectional"))
    )
    (net (code "128") (name "unconnected-(U1A-PC14-OSC32_IN-Pad3)") (class "Default")
      (node (ref "U1") (pin "3") (pinfunction "PC14-OSC32_IN_3") (pintype "bidirectional"))
    )
    (net (code "129") (name "unconnected-(U1A-PC15-OSC32_OUT-Pad4)") (class "Default")
      (node (ref "U1") (pin "4") (pinfunction "PC15-OSC32_OUT_4") (pintype "bidirectional"))
    )
    (net (code "130") (name "unconnected-(U2-~{SE}-Pad6)") (class "Default")
      (node (ref "U2") (pin "6") (pinfunction "~{SE}_6") (pintype "input+no_connect"))
    )
  )
)
